# TLog_TopBat.net
KiCad netlist of a schematic drawn in EAGLE
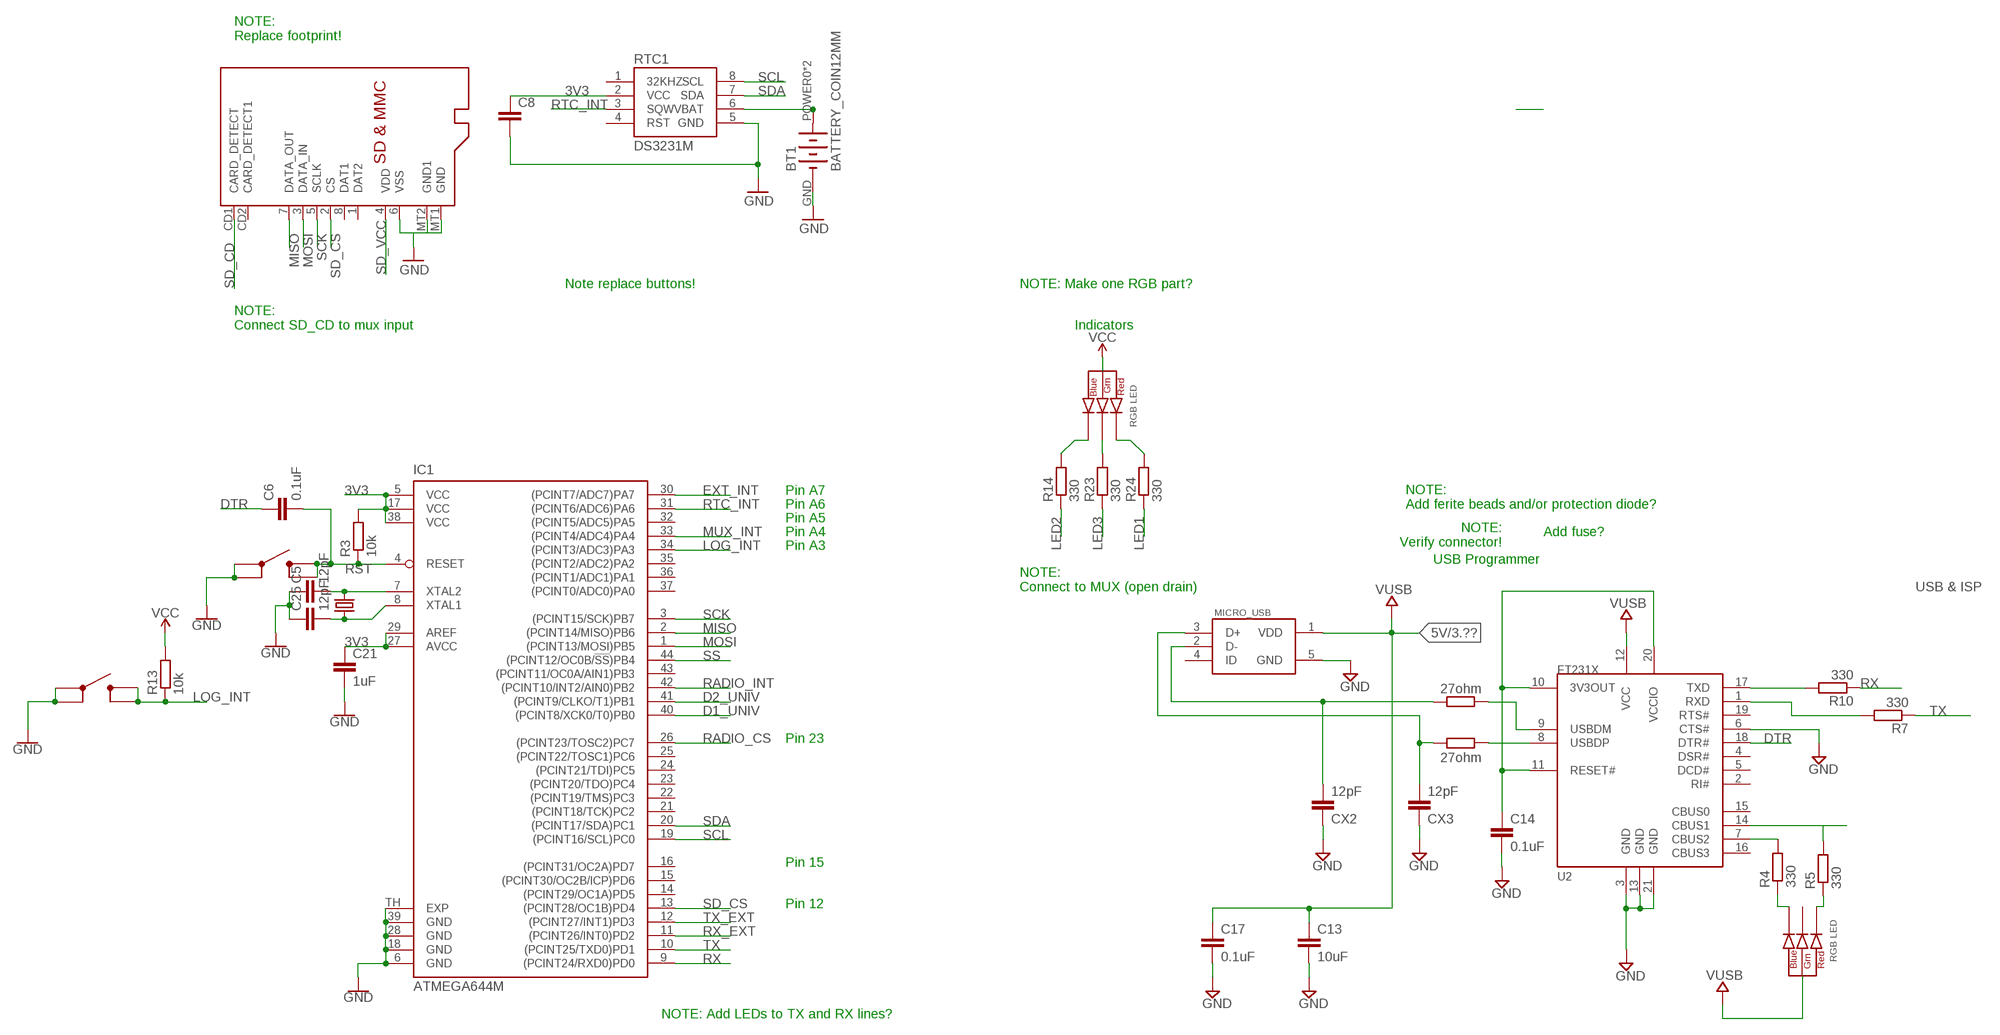
[diagram p0: schematic, sheet 1]
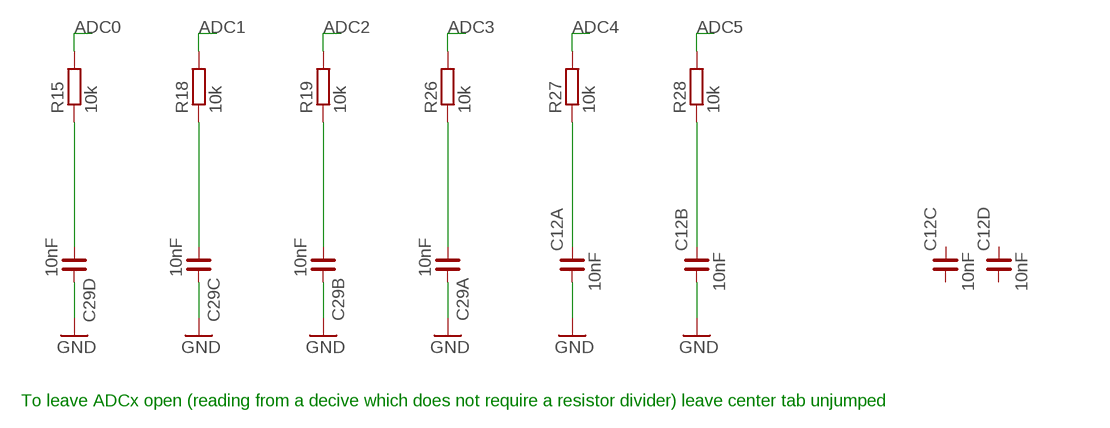
[diagram p1: schematic, sheet 2]
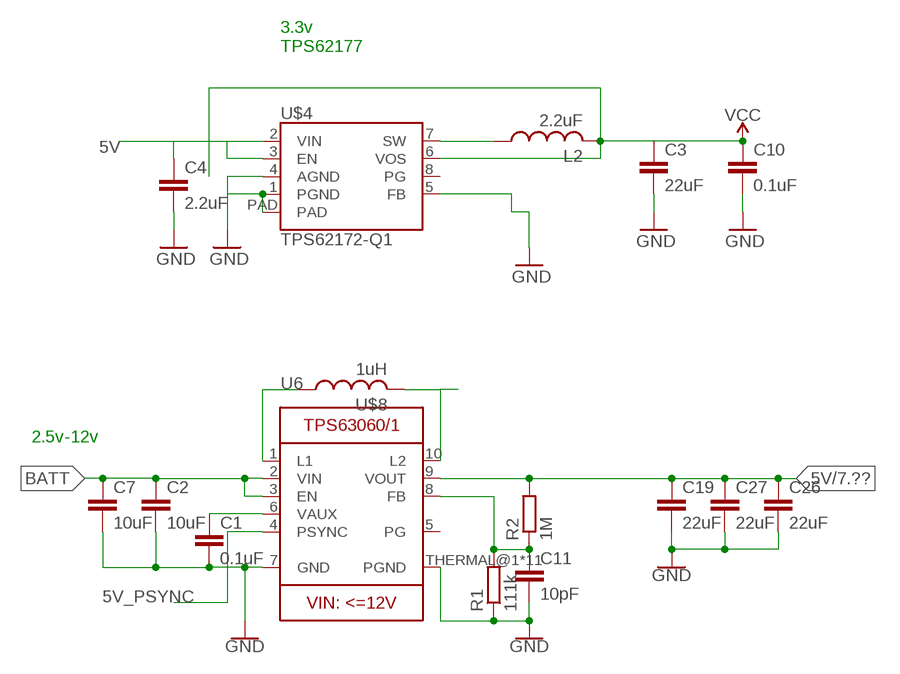
[diagram p2: schematic, sheet 3]
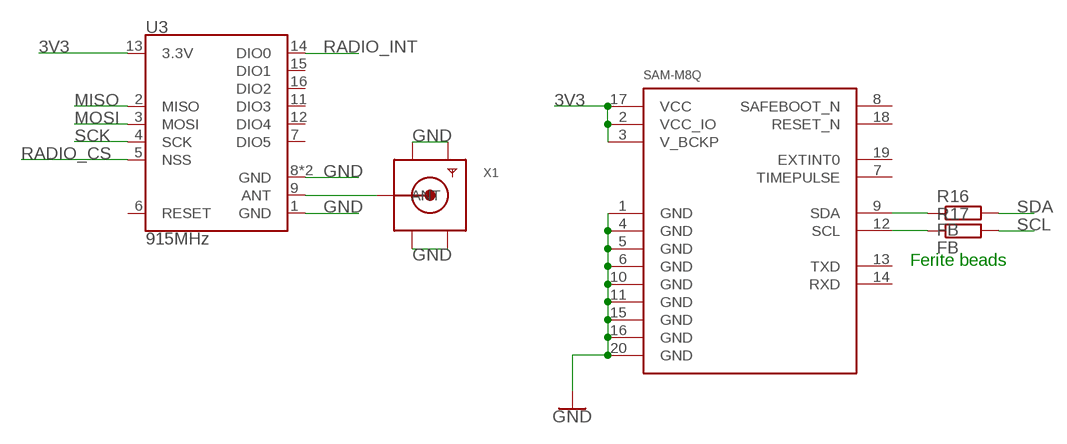
[diagram p3: schematic, sheet 4]
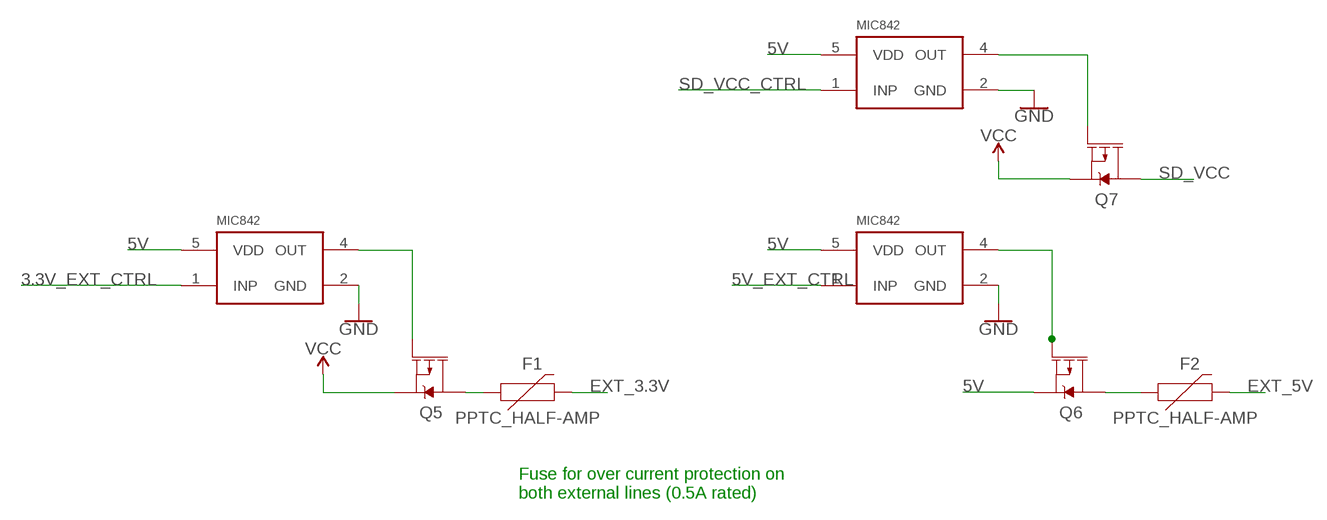
[diagram p4: schematic, sheet 5]
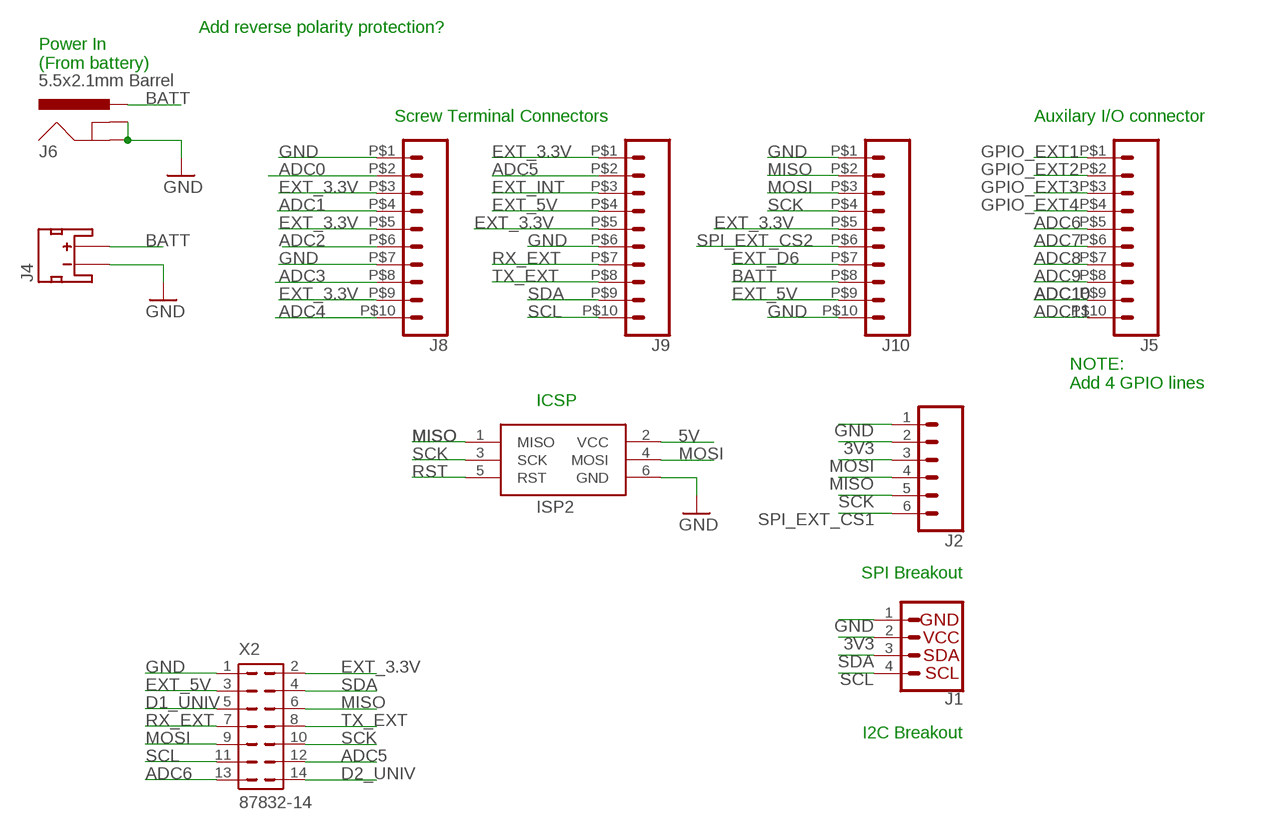
[diagram p5: schematic, sheet 6]
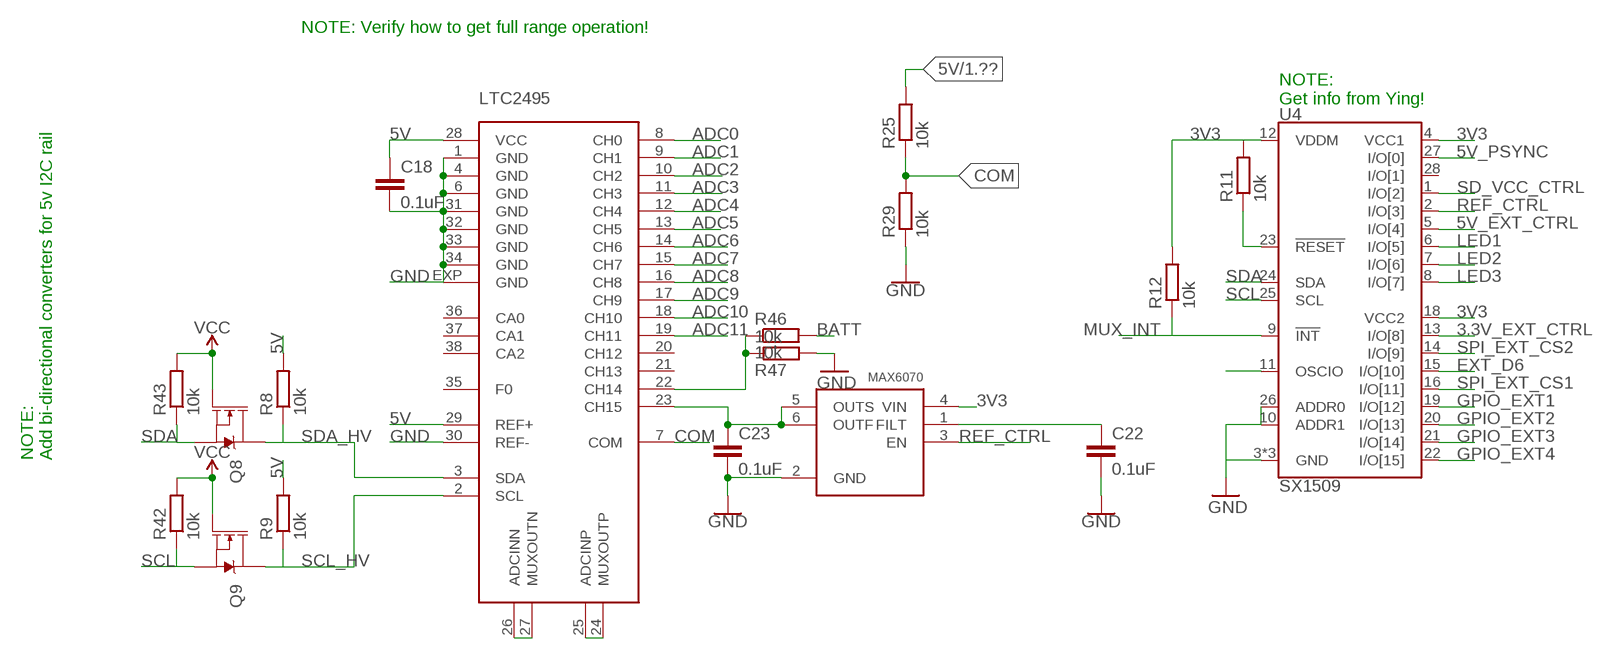
[diagram p6: schematic, sheet 7]

(export (version "E")
  (design (tool "Eeschema 10.0.6"))
  (components
    (comp (ref "C18")
      (value "0.1uF")
      (footprint "eagle-import:C0603")
      (fields (field (name "MF") "Samsung") (field (name "MPN") "CL10B104KO8NNNC"))
      (libsource (lib "eagle-import") (part "C-EUC06030.1UF"))
    )
    (comp (ref "C22")
      (value "0.1uF")
      (footprint "eagle-import:C0603")
      (fields (field (name "MF") "Samsung") (field (name "MPN") "CL10B104KO8NNNC"))
      (libsource (lib "eagle-import") (part "C-EUC06030.1UF"))
    )
    (comp (ref "C23")
      (value "0.1uF")
      (footprint "eagle-import:C0603")
      (fields (field (name "MF") "Samsung") (field (name "MPN") "CL10B104KO8NNNC"))
      (libsource (lib "eagle-import") (part "C-EUC06030.1UF"))
    )
    (comp (ref "Q8")
      (value "MOSFET-NCH-BSS138")
      (footprint "eagle-import:SOT23-3")
      (fields (field (name "MF") "ON Semiconductor") (field (name "MPN") "BSS138LT3G"))
      (libsource (lib "eagle-import") (part "MOSFET-NCH-BSS138"))
    )
    (comp (ref "Q9")
      (value "MOSFET-NCH-BSS138")
      (footprint "eagle-import:SOT23-3")
      (fields (field (name "MF") "ON Semiconductor") (field (name "MPN") "BSS138LT3G"))
      (libsource (lib "eagle-import") (part "MOSFET-NCH-BSS138"))
    )
    (comp (ref "R8")
      (value "10k")
      (footprint "eagle-import:R0603")
      (fields (field (name "MF") "Yageo") (field (name "MPN") "RC0603FR-0710KL"))
      (libsource (lib "eagle-import") (part "R-EU_R060310K"))
    )
    (comp (ref "R9")
      (value "10k")
      (footprint "eagle-import:R0603")
      (fields (field (name "MF") "Yageo") (field (name "MPN") "RC0603FR-0710KL"))
      (libsource (lib "eagle-import") (part "R-EU_R060310K"))
    )
    (comp (ref "R11")
      (value "10k")
      (footprint "eagle-import:R0603")
      (fields (field (name "MF") "Yageo") (field (name "MPN") "RC0603FR-0710KL"))
      (libsource (lib "eagle-import") (part "R-EU_R060310K"))
    )
    (comp (ref "R12")
      (value "10k")
      (footprint "eagle-import:R0603")
      (fields (field (name "MF") "Yageo") (field (name "MPN") "RC0603FR-0710KL"))
      (libsource (lib "eagle-import") (part "R-EU_R060310K"))
    )
    (comp (ref "R25")
      (value "10k")
      (footprint "eagle-import:R0603")
      (fields (field (name "MF") "Yageo") (field (name "MPN") "RC0603FR-0710KL"))
      (libsource (lib "eagle-import") (part "R-EU_R060310K"))
    )
    (comp (ref "R29")
      (value "10k")
      (footprint "eagle-import:R0603")
      (fields (field (name "MF") "Yageo") (field (name "MPN") "RC0603FR-0710KL"))
      (libsource (lib "eagle-import") (part "R-EU_R060310K"))
    )
    (comp (ref "R42")
      (value "10k")
      (footprint "eagle-import:R0603")
      (fields (field (name "MF") "Yageo") (field (name "MPN") "RC0603FR-0710KL"))
      (libsource (lib "eagle-import") (part "R-EU_R060310K"))
    )
    (comp (ref "R43")
      (value "10k")
      (footprint "eagle-import:R0603")
      (fields (field (name "MF") "Yageo") (field (name "MPN") "RC0603FR-0710KL"))
      (libsource (lib "eagle-import") (part "R-EU_R060310K"))
    )
    (comp (ref "R46")
      (value "10k")
      (footprint "eagle-import:R0603")
      (fields (field (name "MF") "Yageo") (field (name "MPN") "RC0603FR-0710KL"))
      (libsource (lib "eagle-import") (part "R-EU_R060310K"))
    )
    (comp (ref "R47")
      (value "10k")
      (footprint "eagle-import:R0603")
      (fields (field (name "MF") "Yageo") (field (name "MPN") "RC0603FR-0710KL"))
      (libsource (lib "eagle-import") (part "R-EU_R060310K"))
    )
    (comp (ref "U$7")
      (value "LTC2495")
      (footprint "eagle-import:QFN38-5X7")
      (fields (field (name "MF") "LT") (field (name "MPN") "LTC2495IUHF#PBF"))
      (libsource (lib "eagle-import") (part "LTC2495"))
    )
    (comp (ref "U$10")
      (value "MAX6070AAUT18")
      (footprint "eagle-import:SOT23-6L")
      (fields (field (name "MF") "Maxim") (field (name "MPN") "MAX6070BAUT18+T"))
      (libsource (lib "eagle-import") (part "MAX6070AAUT18"))
    )
    (comp (ref "U4")
      (value "SX1509")
      (footprint "eagle-import:QFN-28")
      (fields (field (name "MF") "Semtech") (field (name "MPN") "SX1509BIULTRT"))
      (libsource (lib "eagle-import") (part "SX1509"))
    )
    (comp (ref "ISP2")
      (value "AVRISP-6")
      (footprint "eagle-import:AVRISP")
      (fields (field (name "MF") "Amphenol") (field (name "MPN") "67997-206HLF"))
      (libsource (lib "eagle-import") (part "AVRISP-6"))
    )
    (comp (ref "J1")
      (value "I2C_STANDARD")
      (footprint "eagle-import:1X04")
      (libsource (lib "eagle-import") (part "I2C_STANDARD"))
    )
    (comp (ref "J2")
      (value "CONN_06SILK_FEMALE_PTH")
      (footprint "eagle-import:1X06")
      (libsource (lib "eagle-import") (part "CONN_06SILK_FEMALE_PTH"))
    )
    (comp (ref "J4")
      (value "JST_2MM_MALE")
      (footprint "eagle-import:JST-2-SMD")
      (fields (field (name "MF") "JST") (field (name "MPN") "S2B-PH-SM4-TB(LF)(SN)"))
      (libsource (lib "eagle-import") (part "JST_2MM_MALE"))
    )
    (comp (ref "J5")
      (value "CONN_103.5MM")
      (footprint "eagle-import:1X10_3.5MM_SCREW")
      (fields (field (name "MF") "On Shore Technology") (field (name "MPN") "OSTTE100104"))
      (libsource (lib "eagle-import") (part "CONN_103.5MM"))
    )
    (comp (ref "J6")
      (value "5.5x2.1mm Barrel")
      (footprint "eagle-import:POWER_JACK_SMD")
      (fields (field (name "MF") "Wurth") (field (name "MPN") "694106106102"))
      (libsource (lib "eagle-import") (part "POWER_JACKSMD"))
    )
    (comp (ref "J8")
      (value "CONN_103.5MM")
      (footprint "eagle-import:1X10_3.5MM_SCREW")
      (fields (field (name "MF") "On Shore Technology") (field (name "MPN") "OSTTE100104"))
      (libsource (lib "eagle-import") (part "CONN_103.5MM"))
    )
    (comp (ref "J9")
      (value "CONN_103.5MM")
      (footprint "eagle-import:1X10_3.5MM_SCREW")
      (fields (field (name "MF") "On Shore Technology") (field (name "MPN") "OSTTE100104"))
      (libsource (lib "eagle-import") (part "CONN_103.5MM"))
    )
    (comp (ref "J10")
      (value "CONN_103.5MM")
      (footprint "eagle-import:1X10_3.5MM_SCREW")
      (fields (field (name "MF") "On Shore Technology") (field (name "MPN") "OSTTE100104"))
      (libsource (lib "eagle-import") (part "CONN_103.5MM"))
    )
    (comp (ref "X2")
      (value "87832-14")
      (footprint "eagle-import:87832-14")
      (fields (field (name "MF") "Molex") (field (name "MPN") "0791091006"))
      (libsource (lib "eagle-import") (part "87832-14"))
    )
    (comp (ref "C12")
      (value "10nF")
      (footprint "eagle-import:CECJ-1206")
      (fields
        (field (name "DIGIKEY") "445-1854-1-ND")
        (field (name "MF") "TDK")
        (field (name "MPN") "CKCA43X7R1H103M100AA")
      )
      (libsource (lib "eagle-import") (part "CCA_ECJ-1206"))
    )
    (comp (ref "C29")
      (value "10nF")
      (footprint "eagle-import:CECJ-1206")
      (fields
        (field (name "DIGIKEY") "445-1854-1-ND")
        (field (name "MF") "TDK")
        (field (name "MPN") "CKCA43X7R1H103M100AA")
      )
      (libsource (lib "eagle-import") (part "CCA_ECJ-1206"))
    )
    (comp (ref "R15")
      (value "10k")
      (footprint "eagle-import:R0603")
      (fields (field (name "MF") "Yageo") (field (name "MPN") "RC0603FR-0710KL"))
      (libsource (lib "eagle-import") (part "R-EU_R060310K"))
    )
    (comp (ref "R18")
      (value "10k")
      (footprint "eagle-import:R0603")
      (fields (field (name "MF") "Yageo") (field (name "MPN") "RC0603FR-0710KL"))
      (libsource (lib "eagle-import") (part "R-EU_R060310K"))
    )
    (comp (ref "R19")
      (value "10k")
      (footprint "eagle-import:R0603")
      (fields (field (name "MF") "Yageo") (field (name "MPN") "RC0603FR-0710KL"))
      (libsource (lib "eagle-import") (part "R-EU_R060310K"))
    )
    (comp (ref "R26")
      (value "10k")
      (footprint "eagle-import:R0603")
      (fields (field (name "MF") "Yageo") (field (name "MPN") "RC0603FR-0710KL"))
      (libsource (lib "eagle-import") (part "R-EU_R060310K"))
    )
    (comp (ref "R27")
      (value "10k")
      (footprint "eagle-import:R0603")
      (fields (field (name "MF") "Yageo") (field (name "MPN") "RC0603FR-0710KL"))
      (libsource (lib "eagle-import") (part "R-EU_R060310K"))
    )
    (comp (ref "R28")
      (value "10k")
      (footprint "eagle-import:R0603")
      (fields (field (name "MF") "Yageo") (field (name "MPN") "RC0603FR-0710KL"))
      (libsource (lib "eagle-import") (part "R-EU_R060310K"))
    )
    (comp (ref "F1")
      (value "PPTC_HALF-AMP")
      (footprint "eagle-import:1206")
      (fields (field (name "MF") "Bourns") (field (name "MPN") "MF-NSMF020-2"))
      (libsource (lib "eagle-import") (part "PPTC_HALF-AMP"))
    )
    (comp (ref "F2")
      (value "PPTC_HALF-AMP")
      (footprint "eagle-import:1206")
      (fields (field (name "MF") "Bourns") (field (name "MPN") "MF-NSMF020-2"))
      (libsource (lib "eagle-import") (part "PPTC_HALF-AMP"))
    )
    (comp (ref "Q5")
      (value "MOSFET_PCH-IRLML2244")
      (footprint "eagle-import:SOT23-3")
      (fields (field (name "MF") "Fairchild") (field (name "MPN") "FDN360P"))
      (libsource (lib "eagle-import") (part "MOSFET_PCH-IRLML2244"))
    )
    (comp (ref "Q6")
      (value "MOSFET_PCH-IRLML2244")
      (footprint "eagle-import:SOT23-3")
      (fields (field (name "MF") "Fairchild") (field (name "MPN") "FDN360P"))
      (libsource (lib "eagle-import") (part "MOSFET_PCH-IRLML2244"))
    )
    (comp (ref "Q7")
      (value "MOSFET_PCH-IRLML2244")
      (footprint "eagle-import:SOT23-3")
      (fields (field (name "MF") "Fairchild") (field (name "MPN") "FDN360P"))
      (libsource (lib "eagle-import") (part "MOSFET_PCH-IRLML2244"))
    )
    (comp (ref "U$17")
      (value "MIC842")
      (footprint "eagle-import:DCK_R-PDSO-G5")
      (libsource (lib "eagle-import") (part "MIC842"))
    )
    (comp (ref "U$18")
      (value "MIC842")
      (footprint "eagle-import:DCK_R-PDSO-G5")
      (libsource (lib "eagle-import") (part "MIC842"))
    )
    (comp (ref "U$19")
      (value "MIC842")
      (footprint "eagle-import:DCK_R-PDSO-G5")
      (libsource (lib "eagle-import") (part "MIC842"))
    )
    (comp (ref "R16")
      (value "FB")
      (footprint "eagle-import:R0603")
      (fields (field (name "MF") "Samsung") (field (name "MPN") "CIC10P471NC"))
      (libsource (lib "eagle-import") (part "rcl_R-EU_R0603"))
    )
    (comp (ref "R17")
      (value "FB")
      (footprint "eagle-import:R0603")
      (fields (field (name "MF") "Samsung") (field (name "MPN") "CIC10P471NC"))
      (libsource (lib "eagle-import") (part "rcl_R-EU_R0603"))
    )
    (comp (ref "U$6")
      (value "SAM-M8Q")
      (footprint "eagle-import:SAM-M8Q")
      (fields (field (name "MPN") "SAM-M8Q-0") (field (name "MF") "UBlox"))
      (libsource (lib "eagle-import") (part "SAM-M8Q"))
    )
    (comp (ref "U3")
      (value "915MHz")
      (footprint "eagle-import:RFM69HCW-XXXS2")
      (libsource (lib "eagle-import") (part "RFM69HCW-915"))
    )
    (comp (ref "X1")
      (value "SMA_EDGE")
      (footprint "eagle-import:ADAFRUIT_SMA_EDGELAUNCH")
      (fields (field (name "MF") "RF Solutions") (field (name "MPN") "CON-SMA-EDGE-S"))
      (libsource (lib "eagle-import") (part "SMA_EDGE"))
    )
    (comp (ref "BT1")
      (value "BATTERY_COIN12MM")
      (footprint "eagle-import:AWICKERT_LINX_BAT-HLD-012-SMT")
      (fields (field (name "MF") "Linx") (field (name "MPN") "BAT-HLD-012-SMT"))
      (libsource (lib "eagle-import") (part "BATTERY_COIN12MM"))
    )
    (comp (ref "C5")
      (value "12pF")
      (footprint "eagle-import:C0603")
      (fields
        (field (name "MF") "Samsung")
        (field (name "MPN") "CL10C120JB8NNNC")
        (field (name "DIGIKEY") "1276-1254-1-ND")
        (field (name "MF_1") "Samsung")
        (field (name "MPN_1") "CL10C120JB8NNNC")
      )
      (libsource (lib "eagle-import") (part "C-EUC060312PF"))
    )
    (comp (ref "C6")
      (value "0.1uF")
      (footprint "eagle-import:C0603")
      (fields (field (name "MF") "Samsung") (field (name "MPN") "CL10B104KO8NNNC"))
      (libsource (lib "eagle-import") (part "C-EUC06030.1UF"))
    )
    (comp (ref "C8")
      (value "C-EUC0603")
      (footprint "eagle-import:C0603")
      (libsource (lib "eagle-import") (part "C-EUC0603"))
    )
    (comp (ref "C13")
      (value "10uF")
      (footprint "eagle-import:C0805")
      (fields (field (name "MF") "Samsung") (field (name "MPN") "CL21A106KQCLRNC"))
      (libsource (lib "eagle-import") (part "C-EUC080510UF"))
    )
    (comp (ref "C14")
      (value "0.1uF")
      (footprint "eagle-import:C0603")
      (fields (field (name "MF") "Samsung") (field (name "MPN") "CL10B104KO8NNNC"))
      (libsource (lib "eagle-import") (part "C-EUC06030.1UF"))
    )
    (comp (ref "C17")
      (value "0.1uF")
      (footprint "eagle-import:C0603")
      (fields (field (name "MF") "Samsung") (field (name "MPN") "CL10B104KO8NNNC"))
      (libsource (lib "eagle-import") (part "C-EUC06030.1UF"))
    )
    (comp (ref "C21")
      (value "1uF")
      (footprint "eagle-import:C0603")
      (fields
        (field (name "MF") "Samsung")
        (field (name "MPN") "1276-6524-1-ND")
        (field (name "DIGIKEY") "1276-6524-1-ND")
        (field (name "MF_1") "Samsung")
        (field (name "MPN_1") "CL10B105MO8NNWC")
      )
      (libsource (lib "eagle-import") (part "C-EUC06031UF"))
    )
    (comp (ref "C25")
      (value "12pF")
      (footprint "eagle-import:C0603")
      (fields
        (field (name "MF") "Samsung")
        (field (name "MPN") "CL10C120JB8NNNC")
        (field (name "DIGIKEY") "1276-1254-1-ND")
        (field (name "MF_1") "Samsung")
        (field (name "MPN_1") "CL10C120JB8NNNC")
      )
      (libsource (lib "eagle-import") (part "C-EUC060312PF"))
    )
    (comp (ref "CX2")
      (value "12pF")
      (footprint "eagle-import:C0603")
      (fields (field (name "MF") "Samsung") (field (name "MPN") "CL10C120JB8NNNC"))
      (libsource (lib "eagle-import") (part "C-EUC060312PF"))
    )
    (comp (ref "CX3")
      (value "12pF")
      (footprint "eagle-import:C0603")
      (fields (field (name "MF") "Samsung") (field (name "MPN") "CL10C120JB8NNNC"))
      (libsource (lib "eagle-import") (part "C-EUC060312PF"))
    )
    (comp (ref "D+")
      (value "27ohm")
      (footprint "eagle-import:R0603")
      (fields
        (field (name "MF") "Yageo")
        (field (name "MPN") "RC0603FR-0727RL")
        (field (name "VALUE_PART") "27")
      )
      (libsource (lib "eagle-import") (part "R-EU_R060327"))
    )
    (comp (ref "D-")
      (value "27ohm")
      (footprint "eagle-import:R0603")
      (fields
        (field (name "MF") "Yageo")
        (field (name "MPN") "RC0603FR-0727RL")
        (field (name "VALUE_PART") "27")
      )
      (libsource (lib "eagle-import") (part "R-EU_R060327"))
    )
    (comp (ref "IC1")
      (value "ATMEGA644M")
      (footprint "eagle-import:MLF44-TH")
      (fields (field (name "MF") "Atmel") (field (name "MPN") "ATMEGA644PA-MUR"))
      (libsource (lib "eagle-import") (part "ATMEGA644M"))
    )
    (comp (ref "MICRO_USB")
      (value "MICRO_USB_LONGPADS")
      (footprint "eagle-import:10118194-0001LF_10118194-0001LF_LONGER_PADS")
      (libsource (lib "eagle-import") (part "MICRO_USB_LONGPADS"))
    )
    (comp (ref "R3")
      (value "10k")
      (footprint "eagle-import:R0603")
      (fields
        (field (name "MF") "Yageo")
        (field (name "MPN") "RC0603FR-0710KL")
        (field (name "DIGIKEY") "311-10.0KHRCT-ND")
      )
      (libsource (lib "eagle-import") (part "R-EU_R060310K"))
    )
    (comp (ref "R4")
      (value "330")
      (footprint "eagle-import:R0603")
      (fields
        (field (name "MF") "Yageo")
        (field (name "MPN") "RC0603FR-07330RL")
        (field (name "MPN_1") "RC0603FR-07330RL")
      )
      (libsource (lib "eagle-import") (part "R-EU_R0603330"))
    )
    (comp (ref "R5")
      (value "330")
      (footprint "eagle-import:R0603")
      (fields
        (field (name "MF") "Yageo")
        (field (name "MPN") "RC0603FR-07330RL")
        (field (name "DIGIKEY") "311-330HRCT-ND")
        (field (name "MF_1") "Yageo")
        (field (name "MPN_1") "RC0603FR-07330RL")
      )
      (libsource (lib "eagle-import") (part "R-EU_R0603330"))
    )
    (comp (ref "R7")
      (value "330")
      (footprint "eagle-import:R0603")
      (fields
        (field (name "MF") "Yageo")
        (field (name "MPN") "RC0603FR-07330RL")
        (field (name "MPN_1") "RC0603FR-07330RL")
      )
      (libsource (lib "eagle-import") (part "R-EU_R0603330"))
    )
    (comp (ref "R10")
      (value "330")
      (footprint "eagle-import:R0603")
      (fields
        (field (name "MF") "Yageo")
        (field (name "MPN") "RC0603FR-07330RL")
        (field (name "MPN_1") "RC0603FR-07330RL")
      )
      (libsource (lib "eagle-import") (part "R-EU_R0603330"))
    )
    (comp (ref "R13")
      (value "10k")
      (footprint "eagle-import:R0603")
      (fields
        (field (name "MF") "Yageo")
        (field (name "MPN") "RC0603FR-0710KL")
        (field (name "DIGIKEY") "311-10.0KHRCT-ND")
      )
      (libsource (lib "eagle-import") (part "R-EU_R060310K"))
    )
    (comp (ref "R14")
      (value "330")
      (footprint "eagle-import:R0603")
      (fields
        (field (name "MF") "Yageo")
        (field (name "MPN") "RC0603FR-07330RL")
        (field (name "MPN_1") "RC0603FR-07330RL")
      )
      (libsource (lib "eagle-import") (part "R-EU_R0603330"))
    )
    (comp (ref "R23")
      (value "330")
      (footprint "eagle-import:R0603")
      (fields
        (field (name "MF") "Yageo")
        (field (name "MPN") "RC0603FR-07330RL")
        (field (name "MPN_1") "RC0603FR-07330RL")
      )
      (libsource (lib "eagle-import") (part "R-EU_R0603330"))
    )
    (comp (ref "R24")
      (value "330")
      (footprint "eagle-import:R0603")
      (fields
        (field (name "MF") "Yageo")
        (field (name "MPN") "RC0603FR-07330RL")
        (field (name "MPN_1") "RC0603FR-07330RL")
      )
      (libsource (lib "eagle-import") (part "R-EU_R0603330"))
    )
    (comp (ref "RTC1")
      (value "DS3231M")
      (footprint "eagle-import:SO08")
      (fields (field (name "MF") "Maxim") (field (name "MPN") "DS3231MZ+"))
      (libsource (lib "eagle-import") (part "DS3231M"))
    )
    (comp (ref "U$1")
      (value "CRYSTALTXC_8MHZ")
      (footprint "eagle-import:CRYSTAL_5X3.2_2-SMD")
      (fields (field (name "MF") "TXC") (field (name "MPN") "7A-8.000MAAE-T"))
      (libsource (lib "eagle-import") (part "CRYSTALTXC_8MHZ"))
    )
    (comp (ref "U$2")
      (value "MICROSD")
      (footprint "eagle-import:MICROSD")
      (fields (field (name "MF") "3M") (field (name "MPN") "2908-05WB-MG"))
      (libsource (lib "eagle-import") (part "MICROSD"))
    )
    (comp (ref "U$5")
      (value "BUTTON4.2X3.2")
      (footprint "eagle-import:SWITCH_4.2X3.2")
      (libsource (lib "eagle-import") (part "BUTTON4.2X3.2"))
    )
    (comp (ref "U$9")
      (value "BUTTON4.2X3.2")
      (footprint "eagle-import:SWITCH_4.2X3.2")
      (libsource (lib "eagle-import") (part "BUTTON4.2X3.2"))
    )
    (comp (ref "U$15")
      (value "CLVBA-FKA")
      (footprint "eagle-import:CLVBA-FKA")
      (fields (field (name "MF") "Cree") (field (name "MPN") "CLVBA-FKA-CAEDH8BBB7A363"))
      (libsource (lib "eagle-import") (part "CLVBA-FKA"))
    )
    (comp (ref "U$16")
      (value "CLVBA-FKA")
      (footprint "eagle-import:CLVBA-FKA")
      (fields (field (name "MF") "Cree") (field (name "MPN") "CLVBA-FKA-CAEDH8BBB7A363"))
      (libsource (lib "eagle-import") (part "CLVBA-FKA"))
    )
    (comp (ref "U2")
      (value "FT231X-Q")
      (footprint "eagle-import:QFN20")
      (fields (field (name "MF") "FTDI") (field (name "MPN") "FT231XQ-R"))
      (libsource (lib "eagle-import") (part "FT231X-Q"))
    )
    (comp (ref "C1")
      (value "0.1uF")
      (footprint "eagle-import:C0603")
      (fields (field (name "MF") "Samsung") (field (name "MPN") "CL10B104KO8NNNC"))
      (libsource (lib "eagle-import") (part "C-EUC06030.1UF"))
    )
    (comp (ref "C2")
      (value "10uF")
      (footprint "eagle-import:C0805")
      (fields (field (name "MF") "Samsung") (field (name "MPN") "CL21A106KQCLRNC"))
      (libsource (lib "eagle-import") (part "C-EUC080510UF"))
    )
    (comp (ref "C3")
      (value "22uF")
      (footprint "eagle-import:C0805")
      (fields (field (name "MF") "Samsung") (field (name "MPN") "CL21A226KQCLRNC"))
      (libsource (lib "eagle-import") (part "C-EUC080522UF"))
    )
    (comp (ref "C4")
      (value "2.2uF")
      (footprint "eagle-import:C0805")
      (fields (field (name "MF") "Samsung") (field (name "MPN") "CL21A106KQCLRNC"))
      (libsource (lib "eagle-import") (part "C-EUC080510UF"))
    )
    (comp (ref "C7")
      (value "10uF")
      (footprint "eagle-import:C0805")
      (fields (field (name "MF") "Samsung") (field (name "MPN") "CL21A106KQCLRNC"))
      (libsource (lib "eagle-import") (part "C-EUC080510UF"))
    )
    (comp (ref "C10")
      (value "0.1uF")
      (footprint "eagle-import:C0603")
      (fields (field (name "MF") "Samsung") (field (name "MPN") "CL10B104KO8NNNC"))
      (libsource (lib "eagle-import") (part "C-EUC06030.1UF"))
    )
    (comp (ref "C11")
      (value "10pF")
      (footprint "eagle-import:C0603")
      (fields (field (name "MF") "Samsung") (field (name "MPN") "CL10C120JB8NNNC"))
      (libsource (lib "eagle-import") (part "C-EUC060312PF"))
    )
    (comp (ref "C19")
      (value "22uF")
      (footprint "eagle-import:C0805")
      (fields (field (name "MF") "Samsung") (field (name "MPN") "CL21A226KQCLRNC"))
      (libsource (lib "eagle-import") (part "C-EUC080522UF"))
    )
    (comp (ref "C26")
      (value "22uF")
      (footprint "eagle-import:C0805")
      (fields (field (name "MF") "Samsung") (field (name "MPN") "CL21A226KQCLRNC"))
      (libsource (lib "eagle-import") (part "C-EUC080522UF"))
    )
    (comp (ref "C27")
      (value "22uF")
      (footprint "eagle-import:C0805")
      (fields (field (name "MF") "Samsung") (field (name "MPN") "CL21A226KQCLRNC"))
      (libsource (lib "eagle-import") (part "C-EUC080522UF"))
    )
    (comp (ref "L2")
      (value "2.2uF")
      (footprint "eagle-import:0806")
      (fields (field (name "MF") "Wurth") (field (name "MPN") "74438343022"))
      (libsource (lib "eagle-import") (part "INDUCTOR0806"))
    )
    (comp (ref "R1")
      (value "111k")
      (footprint "eagle-import:R0603")
      (fields
        (field (name "DIGIKEY") "311-143KHRCT-ND")
        (field (name "MF") "Yageo")
        (field (name "MPN") "RC0603FR-07143KL")
      )
      (libsource (lib "eagle-import") (part "R-EU_R0603"))
    )
    (comp (ref "R2")
      (value "1M")
      (footprint "eagle-import:R0603")
      (fields
        (field (name "DIGIKEY") "311-953KHRCT-ND")
        (field (name "MF") "Yageo")
        (field (name "MPN") "RC0603FR-07953KL")
      )
      (libsource (lib "eagle-import") (part "R-EU_R0603"))
    )
    (comp (ref "U$4")
      (value "TPS62172-Q1")
      (footprint "eagle-import:WSON-8-PAD")
      (fields (field (name "MF") "TI") (field (name "MPN") "TPS62172QDSGRQ1"))
      (libsource (lib "eagle-import") (part "TPS6217-Q12"))
    )
    (comp (ref "U$8")
      (value "1uH")
      (footprint "eagle-import:WE-MAIA(4.1X4.1)")
      (fields (field (name "MF") "Wurth") (field (name "MPN") "78438356010"))
      (libsource (lib "eagle-import") (part "INDUCTORMAIA_4.1X4.1"))
    )
    (comp (ref "U6")
      (value "TPS63060")
      (footprint "eagle-import:PWSON-N10")
      (fields (field (name "MF") "TI") (field (name "MPN") "TPS63060DSCR"))
      (libsource (lib "eagle-import") (part "TPS63060"))
    )
  )
  (nets
    (net (code "1") (name "3.3V_EXT_CTRL") (class "Default")
      (node (ref "U$18") (pin "1") (pinfunction "INP_1") (pintype "input"))
      (node (ref "U4") (pin "13") (pinfunction "I/O[8]_13") (pintype "bidirectional"))
    )
    (net (code "2") (name "3V3") (class "Default")
      (node (ref "C10") (pin "1") (pinfunction "1_1") (pintype "passive"))
      (node (ref "C21") (pin "1") (pinfunction "1_1") (pintype "passive"))
      (node (ref "C3") (pin "1") (pinfunction "1_1") (pintype "passive"))
      (node (ref "C8") (pin "1") (pinfunction "1_1") (pintype "passive"))
      (node (ref "IC1") (pin "17") (pinfunction "VCC_17") (pintype "power_in"))
      (node (ref "IC1") (pin "27") (pinfunction "AVCC_27") (pintype "power_in"))
      (node (ref "IC1") (pin "29") (pinfunction "AREF_29") (pintype "passive"))
      (node (ref "IC1") (pin "38") (pinfunction "VCC_38") (pintype "power_in"))
      (node (ref "IC1") (pin "5") (pinfunction "VCC_5") (pintype "power_in"))
      (node (ref "J1") (pin "2") (pinfunction "2_2") (pintype "power_in"))
      (node (ref "J2") (pin "2") (pinfunction "2_2") (pintype "passive"))
      (node (ref "L2") (pin "P$2") (pinfunction "2_P$2") (pintype "passive"))
      (node (ref "Q5") (pin "2") (pinfunction "S_2") (pintype "bidirectional"))
      (node (ref "Q7") (pin "2") (pinfunction "S_2") (pintype "bidirectional"))
      (node (ref "Q8") (pin "1") (pinfunction "G_1") (pintype "bidirectional"))
      (node (ref "Q9") (pin "1") (pinfunction "G_1") (pintype "bidirectional"))
      (node (ref "R11") (pin "2") (pinfunction "2_2") (pintype "passive"))
      (node (ref "R12") (pin "2") (pinfunction "2_2") (pintype "passive"))
      (node (ref "R13") (pin "2") (pinfunction "2_2") (pintype "passive"))
      (node (ref "R3") (pin "2") (pinfunction "2_2") (pintype "passive"))
      (node (ref "R42") (pin "2") (pinfunction "2_2") (pintype "passive"))
      (node (ref "R43") (pin "2") (pinfunction "2_2") (pintype "passive"))
      (node (ref "RTC1") (pin "2") (pinfunction "VCC_2") (pintype "power_in"))
      (node (ref "U$10") (pin "4") (pinfunction "VIN_4") (pintype "bidirectional"))
      (node (ref "U$15") (pin "2") (pinfunction "ANODE_2") (pintype "bidirectional"))
      (node (ref "U$4") (pin "6") (pinfunction "VOS_6") (pintype "bidirectional"))
      (node (ref "U$6") (pin "17") (pinfunction "VCC_17") (pintype "bidirectional"))
      (node (ref "U$6") (pin "2") (pinfunction "VCC_IO_2") (pintype "bidirectional"))
      (node (ref "U$6") (pin "3") (pinfunction "V_BCKP_3") (pintype "bidirectional"))
      (node (ref "U3") (pin "13") (pinfunction "3.3V_13") (pintype "power_in"))
      (node (ref "U4") (pin "12") (pinfunction "VDDM_12") (pintype "bidirectional"))
      (node (ref "U4") (pin "18") (pinfunction "VCC2_18") (pintype "bidirectional"))
      (node (ref "U4") (pin "4") (pinfunction "VCC1_4") (pintype "bidirectional"))
    )
    (net (code "3") (name "5V") (class "Default")
      (node (ref "C13") (pin "1") (pinfunction "1_1") (pintype "passive"))
      (node (ref "C17") (pin "1") (pinfunction "1_1") (pintype "passive"))
      (node (ref "C18") (pin "1") (pinfunction "1_1") (pintype "passive"))
      (node (ref "C19") (pin "1") (pinfunction "1_1") (pintype "passive"))
      (node (ref "C26") (pin "1") (pinfunction "1_1") (pintype "passive"))
      (node (ref "C27") (pin "1") (pinfunction "1_1") (pintype "passive"))
      (node (ref "C4") (pin "1") (pinfunction "1_1") (pintype "passive"))
      (node (ref "ISP2") (pin "2") (pinfunction "VCC_2") (pintype "power_in"))
      (node (ref "MICRO_USB") (pin "1") (pinfunction "VDD_1") (pintype "power_in"))
      (node (ref "Q6") (pin "2") (pinfunction "S_2") (pintype "bidirectional"))
      (node (ref "R2") (pin "2") (pinfunction "2_2") (pintype "passive"))
      (node (ref "R25") (pin "2") (pinfunction "2_2") (pintype "passive"))
      (node (ref "R8") (pin "2") (pinfunction "2_2") (pintype "passive"))
      (node (ref "R9") (pin "2") (pinfunction "2_2") (pintype "passive"))
      (node (ref "U$16") (pin "2") (pinfunction "ANODE_2") (pintype "bidirectional"))
      (node (ref "U$17") (pin "5") (pinfunction "VDD_5") (pintype "power_in"))
      (node (ref "U$18") (pin "5") (pinfunction "VDD_5") (pintype "power_in"))
      (node (ref "U$19") (pin "5") (pinfunction "VDD_5") (pintype "power_in"))
      (node (ref "U$4") (pin "2") (pinfunction "VIN_2") (pintype "bidirectional"))
      (node (ref "U$4") (pin "3") (pinfunction "EN_3") (pintype "bidirectional"))
      (node (ref "U$7") (pin "28") (pinfunction "VCC_28") (pintype "power_in"))
      (node (ref "U$7") (pin "29") (pinfunction "REF+_29") (pintype "input"))
      (node (ref "U2") (pin "12") (pinfunction "VCC_12") (pintype "bidirectional"))
      (node (ref "U6") (pin "9") (pinfunction "VOUT_9") (pintype "power_in"))
    )
    (net (code "4") (name "5V_EXT_CTRL") (class "Default")
      (node (ref "U$17") (pin "1") (pinfunction "INP_1") (pintype "input"))
      (node (ref "U4") (pin "5") (pinfunction "I/O[4]_5") (pintype "bidirectional"))
    )
    (net (code "5") (name "5V_PSYNC") (class "Default")
      (node (ref "U4") (pin "27") (pinfunction "I/O[0]_27") (pintype "bidirectional"))
      (node (ref "U6") (pin "4") (pinfunction "PSYNC_4") (pintype "input"))
    )
    (net (code "6") (name "ADC0") (class "Default")
      (node (ref "J8") (pin "P$2") (pinfunction "2_P$2") (pintype "passive"))
      (node (ref "R15") (pin "2") (pinfunction "2_2") (pintype "passive"))
      (node (ref "U$7") (pin "8") (pinfunction "CH0_8") (pintype "input"))
    )
    (net (code "7") (name "ADC1") (class "Default")
      (node (ref "J8") (pin "P$4") (pinfunction "4_P$4") (pintype "passive"))
      (node (ref "R18") (pin "2") (pinfunction "2_2") (pintype "passive"))
      (node (ref "U$7") (pin "9") (pinfunction "CH1_9") (pintype "input"))
    )
    (net (code "8") (name "ADC2") (class "Default")
      (node (ref "J8") (pin "P$6") (pinfunction "6_P$6") (pintype "passive"))
      (node (ref "R19") (pin "2") (pinfunction "2_2") (pintype "passive"))
      (node (ref "U$7") (pin "10") (pinfunction "CH2_10") (pintype "input"))
    )
    (net (code "9") (name "ADC3") (class "Default")
      (node (ref "J8") (pin "P$8") (pinfunction "8_P$8") (pintype "passive"))
      (node (ref "R26") (pin "2") (pinfunction "2_2") (pintype "passive"))
      (node (ref "U$7") (pin "11") (pinfunction "CH3_11") (pintype "input"))
    )
    (net (code "10") (name "ADC4") (class "Default")
      (node (ref "J8") (pin "P$10") (pinfunction "10_P$10") (pintype "passive"))
      (node (ref "R27") (pin "2") (pinfunction "2_2") (pintype "passive"))
      (node (ref "U$7") (pin "12") (pinfunction "CH4_12") (pintype "input"))
    )
    (net (code "11") (name "ADC5") (class "Default")
      (node (ref "J9") (pin "P$2") (pinfunction "2_P$2") (pintype "passive"))
      (node (ref "R28") (pin "2") (pinfunction "2_2") (pintype "passive"))
      (node (ref "U$7") (pin "13") (pinfunction "CH5_13") (pintype "input"))
      (node (ref "X2") (pin "12") (pinfunction "12_12") (pintype "passive"))
    )
    (net (code "12") (name "ADC6") (class "Default")
      (node (ref "J5") (pin "P$5") (pinfunction "5_P$5") (pintype "passive"))
      (node (ref "U$7") (pin "14") (pinfunction "CH6_14") (pintype "input"))
      (node (ref "X2") (pin "13") (pinfunction "13_13") (pintype "passive"))
    )
    (net (code "13") (name "ADC7") (class "Default")
      (node (ref "J5") (pin "P$6") (pinfunction "6_P$6") (pintype "passive"))
      (node (ref "U$7") (pin "15") (pinfunction "CH7_15") (pintype "input"))
    )
    (net (code "14") (name "ADC8") (class "Default")
      (node (ref "J5") (pin "P$7") (pinfunction "7_P$7") (pintype "passive"))
      (node (ref "U$7") (pin "16") (pinfunction "CH8_16") (pintype "input"))
    )
    (net (code "15") (name "ADC9") (class "Default")
      (node (ref "J5") (pin "P$8") (pinfunction "8_P$8") (pintype "passive"))
      (node (ref "U$7") (pin "17") (pinfunction "CH9_17") (pintype "input"))
    )
    (net (code "16") (name "ADC10") (class "Default")
      (node (ref "J5") (pin "P$9") (pinfunction "9_P$9") (pintype "passive"))
      (node (ref "U$7") (pin "18") (pinfunction "CH10_18") (pintype "input"))
    )
    (net (code "17") (name "ADC11") (class "Default")
      (node (ref "J5") (pin "P$10") (pinfunction "10_P$10") (pintype "passive"))
      (node (ref "U$7") (pin "19") (pinfunction "CH11_19") (pintype "input"))
    )
    (net (code "18") (name "BATT") (class "Default")
      (node (ref "C2") (pin "1") (pinfunction "1_1") (pintype "passive"))
      (node (ref "C7") (pin "1") (pinfunction "1_1") (pintype "passive"))
      (node (ref "J10") (pin "P$8") (pinfunction "8_P$8") (pintype "passive"))
      (node (ref "J4") (pin "2") (pinfunction "+_2") (pintype "bidirectional"))
      (node (ref "J6") (pin "VIN0") (pinfunction "PWR_VIN0") (pintype "bidirectional"))
      (node (ref "R46") (pin "2") (pinfunction "2_2") (pintype "passive"))
      (node (ref "U6") (pin "2") (pinfunction "VIN_2") (pintype "power_in"))
      (node (ref "U6") (pin "3") (pinfunction "EN_3") (pintype "input"))
    )
    (net (code "19") (name "COM") (class "Default")
      (node (ref "R25") (pin "1") (pinfunction "1_1") (pintype "passive"))
      (node (ref "R29") (pin "2") (pinfunction "2_2") (pintype "passive"))
      (node (ref "U$7") (pin "7") (pinfunction "COM_7") (pintype "input"))
    )
    (net (code "20") (name "D1_UNIV") (class "Default")
      (node (ref "IC1") (pin "40") (pinfunction "(PCINT8/XCK0/T0)PB0_40") (pintype "bidirectional"))
      (node (ref "X2") (pin "5") (pinfunction "5_5") (pintype "passive"))
    )
    (net (code "21") (name "D2_UNIV") (class "Default")
      (node (ref "IC1") (pin "41") (pinfunction "(PCINT9/CLKO/T1)PB1_41") (pintype "bidirectional"))
      (node (ref "X2") (pin "14") (pinfunction "14_14") (pintype "passive"))
    )
    (net (code "22") (name "DTR") (class "Default")
      (node (ref "C6") (pin "1") (pinfunction "1_1") (pintype "passive"))
      (node (ref "U2") (pin "18") (pinfunction "DTR#_18") (pintype "bidirectional"))
    )
    (net (code "23") (name "EXT_3.3V") (class "Default")
      (node (ref "F1") (pin "2") (pinfunction "2_2") (pintype "bidirectional"))
      (node (ref "J10") (pin "P$5") (pinfunction "5_P$5") (pintype "passive"))
      (node (ref "J8") (pin "P$3") (pinfunction "3_P$3") (pintype "passive"))
      (node (ref "J8") (pin "P$5") (pinfunction "5_P$5") (pintype "passive"))
      (node (ref "J8") (pin "P$9") (pinfunction "9_P$9") (pintype "passive"))
      (node (ref "J9") (pin "P$1") (pinfunction "1_P$1") (pintype "passive"))
      (node (ref "J9") (pin "P$5") (pinfunction "5_P$5") (pintype "passive"))
      (node (ref "X2") (pin "2") (pinfunction "2_2") (pintype "passive"))
    )
    (net (code "24") (name "EXT_5V") (class "Default")
      (node (ref "F2") (pin "2") (pinfunction "2_2") (pintype "bidirectional"))
      (node (ref "J10") (pin "P$9") (pinfunction "9_P$9") (pintype "passive"))
      (node (ref "J9") (pin "P$4") (pinfunction "4_P$4") (pintype "passive"))
      (node (ref "X2") (pin "3") (pinfunction "3_3") (pintype "passive"))
    )
    (net (code "25") (name "EXT_D6") (class "Default")
      (node (ref "J10") (pin "P$7") (pinfunction "7_P$7") (pintype "passive"))
      (node (ref "U4") (pin "15") (pinfunction "I/O[10]_15") (pintype "bidirectional"))
    )
    (net (code "26") (name "EXT_INT") (class "Default")
      (node (ref "IC1") (pin "30") (pinfunction "(PCINT7/ADC7)PA7_30") (pintype "bidirectional"))
      (node (ref "J9") (pin "P$3") (pinfunction "3_P$3") (pintype "passive"))
    )
    (net (code "27") (name "GND") (class "Default")
      (node (ref "BT1") (pin "GND") (pinfunction "-_GND") (pintype "passive"))
      (node (ref "C1") (pin "2") (pinfunction "2_2") (pintype "passive"))
      (node (ref "C10") (pin "2") (pinfunction "2_2") (pintype "passive"))
      (node (ref "C11") (pin "2") (pinfunction "2_2") (pintype "passive"))
      (node (ref "C12") (pin "A1") (pinfunction "1_A1") (pintype "passive"))
      (node (ref "C12") (pin "B1") (pinfunction "1_B1") (pintype "passive"))
      (node (ref "C13") (pin "2") (pinfunction "2_2") (pintype "passive"))
      (node (ref "C14") (pin "2") (pinfunction "2_2") (pintype "passive"))
      (node (ref "C17") (pin "2") (pinfunction "2_2") (pintype "passive"))
      (node (ref "C18") (pin "2") (pinfunction "2_2") (pintype "passive"))
      (node (ref "C19") (pin "2") (pinfunction "2_2") (pintype "passive"))
      (node (ref "C2") (pin "2") (pinfunction "2_2") (pintype "passive"))
      (node (ref "C21") (pin "2") (pinfunction "2_2") (pintype "passive"))
      (node (ref "C22") (pin "2") (pinfunction "2_2") (pintype "passive"))
      (node (ref "C23") (pin "2") (pinfunction "2_2") (pintype "passive"))
      (node (ref "C25") (pin "1") (pinfunction "1_1") (pintype "passive"))
      (node (ref "C26") (pin "2") (pinfunction "2_2") (pintype "passive"))
      (node (ref "C27") (pin "2") (pinfunction "2_2") (pintype "passive"))
      (node (ref "C29") (pin "A2") (pinfunction "2_A2") (pintype "passive"))
      (node (ref "C29") (pin "B2") (pinfunction "2_B2") (pintype "passive"))
      (node (ref "C29") (pin "C2") (pinfunction "2_C2") (pintype "passive"))
      (node (ref "C29") (pin "D2") (pinfunction "2_D2") (pintype "passive"))
      (node (ref "C3") (pin "2") (pinfunction "2_2") (pintype "passive"))
      (node (ref "C4") (pin "2") (pinfunction "2_2") (pintype "passive"))
      (node (ref "C5") (pin "1") (pinfunction "1_1") (pintype "passive"))
      (node (ref "C7") (pin "2") (pinfunction "2_2") (pintype "passive"))
      (node (ref "C8") (pin "2") (pinfunction "2_2") (pintype "passive"))
      (node (ref "CX2") (pin "1") (pinfunction "1_1") (pintype "passive"))
      (node (ref "CX3") (pin "1") (pinfunction "1_1") (pintype "passive"))
      (node (ref "IC1") (pin "18") (pinfunction "GND_18") (pintype "power_in"))
      (node (ref "IC1") (pin "28") (pinfunction "GND_28") (pintype "power_in"))
      (node (ref "IC1") (pin "39") (pinfunction "GND_39") (pintype "power_in"))
      (node (ref "IC1") (pin "6") (pinfunction "GND_6") (pintype "power_in"))
      (node (ref "IC1") (pin "TH") (pinfunction "EXP_TH") (pintype "power_in"))
      (node (ref "ISP2") (pin "6") (pinfunction "GND_6") (pintype "power_in"))
      (node (ref "J1") (pin "1") (pinfunction "1_1") (pintype "power_in"))
      (node (ref "J10") (pin "P$1") (pinfunction "1_P$1") (pintype "passive"))
      (node (ref "J10") (pin "P$10") (pinfunction "10_P$10") (pintype "passive"))
      (node (ref "J2") (pin "1") (pinfunction "1_1") (pintype "passive"))
      (node (ref "J4") (pin "1") (pinfunction "-_1") (pintype "bidirectional"))
      (node (ref "J6") (pin "GND") (pinfunction "GNDBREAK_GND") (pintype "bidirectional"))
      (node (ref "J6") (pin "P$4") (pinfunction "GND_P$4") (pintype "bidirectional"))
      (node (ref "J8") (pin "P$1") (pinfunction "1_P$1") (pintype "passive"))
      (node (ref "J8") (pin "P$7") (pinfunction "7_P$7") (pintype "passive"))
      (node (ref "J9") (pin "P$6") (pinfunction "6_P$6") (pintype "passive"))
      (node (ref "MICRO_USB") (pin "5") (pinfunction "GND_5") (pintype "power_in"))
      (node (ref "R1") (pin "1") (pinfunction "1_1") (pintype "passive"))
      (node (ref "R29") (pin "1") (pinfunction "1_1") (pintype "passive"))
      (node (ref "R47") (pin "2") (pinfunction "2_2") (pintype "passive"))
      (node (ref "RTC1") (pin "5") (pinfunction "GND_5") (pintype "power_in"))
      (node (ref "U$10") (pin "2") (pinfunction "GND_2") (pintype "bidirectional"))
      (node (ref "U$17") (pin "2") (pinfunction "GND_2") (pintype "power_in"))
      (node (ref "U$18") (pin "2") (pinfunction "GND_2") (pintype "power_in"))
      (node (ref "U$19") (pin "2") (pinfunction "GND_2") (pintype "power_in"))
      (node (ref "U$2") (pin "6") (pinfunction "VSS_6") (pintype "power_in"))
      (node (ref "U$2") (pin "MT1") (pinfunction "GND_MT1") (pintype "power_in"))
      (node (ref "U$2") (pin "MT2") (pinfunction "GND1_MT2") (pintype "power_in"))
      (node (ref "U$4") (pin "1") (pinfunction "PGND_1") (pintype "bidirectional"))
      (node (ref "U$4") (pin "4") (pinfunction "AGND_4") (pintype "bidirectional"))
      (node (ref "U$4") (pin "5") (pinfunction "FB_5") (pintype "bidirectional"))
      (node (ref "U$4") (pin "PAD") (pinfunction "PAD_PAD") (pintype "bidirectional"))
      (node (ref "U$5") (pin "1") (pinfunction "1_1") (pintype "bidirectional"))
      (node (ref "U$5") (pin "2") (pinfunction "2_2") (pintype "bidirectional"))
      (node (ref "U$6") (pin "1") (pinfunction "GND_1") (pintype "bidirectional"))
      (node (ref "U$6") (pin "10") (pinfunction "GND_10") (pintype "bidirectional"))
      (node (ref "U$6") (pin "11") (pinfunction "GND_11") (pintype "bidirectional"))
      (node (ref "U$6") (pin "15") (pinfunction "GND_15") (pintype "bidirectional"))
      (node (ref "U$6") (pin "16") (pinfunction "GND_16") (pintype "bidirectional"))
      (node (ref "U$6") (pin "20") (pinfunction "GND_20") (pintype "bidirectional"))
      (node (ref "U$6") (pin "4") (pinfunction "GND_4") (pintype "bidirectional"))
      (node (ref "U$6") (pin "5") (pinfunction "GND_5") (pintype "bidirectional"))
      (node (ref "U$6") (pin "6") (pinfunction "GND_6") (pintype "bidirectional"))
      (node (ref "U$7") (pin "1") (pinfunction "GND_1") (pintype "power_in"))
      (node (ref "U$7") (pin "30") (pinfunction "REF-_30") (pintype "input"))
      (node (ref "U$7") (pin "31") (pinfunction "GND_31") (pintype "power_in"))
      (node (ref "U$7") (pin "32") (pinfunction "GND_32") (pintype "power_in"))
      (node (ref "U$7") (pin "33") (pinfunction "GND_33") (pintype "power_in"))
      (node (ref "U$7") (pin "34") (pinfunction "GND_34") (pintype "power_in"))
      (node (ref "U$7") (pin "4") (pinfunction "GND_4") (pintype "power_in"))
      (node (ref "U$7") (pin "6") (pinfunction "GND_6") (pintype "power_in"))
      (node (ref "U$7") (pin "EXP") (pinfunction "GND_EXP") (pintype "power_in"))
      (node (ref "U$9") (pin "1") (pinfunction "1_1") (pintype "bidirectional"))
      (node (ref "U$9") (pin "2") (pinfunction "2_2") (pintype "bidirectional"))
      (node (ref "U2") (pin "13") (pinfunction "GND_13") (pintype "bidirectional"))
      (node (ref "U2") (pin "21") (pinfunction "GND_21") (pintype "bidirectional"))
      (node (ref "U2") (pin "3") (pinfunction "GND_3") (pintype "bidirectional"))
      (node (ref "U2") (pin "6") (pinfunction "CTS#_6") (pintype "bidirectional"))
      (node (ref "U3") (pin "1") (pinfunction "GND_1") (pintype "power_in"))
      (node (ref "U3") (pin "10") (pinfunction "GND_10") (pintype "power_in"))
      (node (ref "U3") (pin "8") (pinfunction "GND_8") (pintype "power_in"))
      (node (ref "U4") (pin "10") (pinfunction "ADDR1_10") (pintype "bidirectional"))
      (node (ref "U4") (pin "17") (pinfunction "GND_17") (pintype "bidirectional"))
      (node (ref "U4") (pin "26") (pinfunction "ADDR0_26") (pintype "bidirectional"))
      (node (ref "U4") (pin "29") (pinfunction "GND_29") (pintype "bidirectional"))
      (node (ref "U4") (pin "3") (pinfunction "GND_3") (pintype "bidirectional"))
      (node (ref "U6") (pin "7") (pinfunction "GND_7") (pintype "power_in"))
      (node (ref "U6") (pin "THERMAL@1") (pinfunction "PGND_THERMAL@1") (pintype "power_in"))
      (node (ref "U6") (pin "THERMAL@10") (pinfunction "PGND_THERMAL@10") (pintype "power_in"))
      (node (ref "U6") (pin "THERMAL@11") (pinfunction "PGND_THERMAL@11") (pintype "power_in"))
      (node (ref "U6") (pin "THERMAL@12") (pinfunction "PGND_THERMAL@12") (pintype "power_in"))
      (node (ref "U6") (pin "THERMAL@13") (pinfunction "PGND_THERMAL@13") (pintype "power_in"))
      (node (ref "U6") (pin "THERMAL@14") (pinfunction "PGND_THERMAL@14") (pintype "power_in"))
      (node (ref "U6") (pin "THERMAL@5") (pinfunction "PGND_THERMAL@5") (pintype "power_in"))
      (node (ref "U6") (pin "THERMAL@6") (pinfunction "PGND_THERMAL@6") (pintype "power_in"))
      (node (ref "U6") (pin "THERMAL@7") (pinfunction "PGND_THERMAL@7") (pintype "power_in"))
      (node (ref "U6") (pin "THERMAL@8") (pinfunction "PGND_THERMAL@8") (pintype "power_in"))
      (node (ref "U6") (pin "THERMAL@9") (pinfunction "PGND_THERMAL@9") (pintype "power_in"))
      (node (ref "X1") (pin "GND@1") (pinfunction "GND4_GND@1") (pintype "power_in"))
      (node (ref "X1") (pin "GND@2") (pinfunction "GND3_GND@2") (pintype "power_in"))
      (node (ref "X1") (pin "GND@3") (pinfunction "GND2_GND@3") (pintype "power_in"))
      (node (ref "X1") (pin "GND@4") (pinfunction "GND1_GND@4") (pintype "power_in"))
      (node (ref "X2") (pin "1") (pinfunction "1_1") (pintype "passive"))
    )
    (net (code "28") (name "GPIO_EXT1") (class "Default")
      (node (ref "J5") (pin "P$1") (pinfunction "1_P$1") (pintype "passive"))
      (node (ref "U4") (pin "19") (pinfunction "I/O[12]_19") (pintype "bidirectional"))
    )
    (net (code "29") (name "GPIO_EXT2") (class "Default")
      (node (ref "J5") (pin "P$2") (pinfunction "2_P$2") (pintype "passive"))
      (node (ref "U4") (pin "20") (pinfunction "I/O[13]_20") (pintype "bidirectional"))
    )
    (net (code "30") (name "GPIO_EXT3") (class "Default")
      (node (ref "J5") (pin "P$3") (pinfunction "3_P$3") (pintype "passive"))
      (node (ref "U4") (pin "21") (pinfunction "I/O[14]_21") (pintype "bidirectional"))
    )
    (net (code "31") (name "GPIO_EXT4") (class "Default")
      (node (ref "J5") (pin "P$4") (pinfunction "4_P$4") (pintype "passive"))
      (node (ref "U4") (pin "22") (pinfunction "I/O[15]_22") (pintype "bidirectional"))
    )
    (net (code "32") (name "LED1") (class "Default")
      (node (ref "R24") (pin "1") (pinfunction "1_1") (pintype "passive"))
      (node (ref "U4") (pin "6") (pinfunction "I/O[5]_6") (pintype "bidirectional"))
    )
    (net (code "33") (name "LED2") (class "Default")
      (node (ref "R14") (pin "1") (pinfunction "1_1") (pintype "passive"))
      (node (ref "U4") (pin "7") (pinfunction "I/O[6]_7") (pintype "bidirectional"))
    )
    (net (code "34") (name "LED3") (class "Default")
      (node (ref "R23") (pin "1") (pinfunction "1_1") (pintype "passive"))
      (node (ref "U4") (pin "8") (pinfunction "I/O[7]_8") (pintype "bidirectional"))
    )
    (net (code "35") (name "LOG_INT") (class "Default")
      (node (ref "IC1") (pin "34") (pinfunction "(PCINT3/ADC3)PA3_34") (pintype "bidirectional"))
      (node (ref "R13") (pin "1") (pinfunction "1_1") (pintype "passive"))
      (node (ref "U$5") (pin "3") (pinfunction "4_3") (pintype "bidirectional"))
      (node (ref "U$5") (pin "4") (pinfunction "3_4") (pintype "bidirectional"))
    )
    (net (code "36") (name "MISO") (class "Default")
      (node (ref "IC1") (pin "2") (pinfunction "(PCINT14/MISO)PB6_2") (pintype "bidirectional"))
      (node (ref "ISP2") (pin "1") (pinfunction "MISO_1") (pintype "input"))
      (node (ref "J10") (pin "P$2") (pinfunction "2_P$2") (pintype "passive"))
      (node (ref "J2") (pin "4") (pinfunction "4_4") (pintype "passive"))
      (node (ref "U$2") (pin "7") (pinfunction "DATA_OUT_7") (pintype "output"))
      (node (ref "U3") (pin "2") (pinfunction "MISO_2") (pintype "bidirectional"))
      (node (ref "X2") (pin "6") (pinfunction "6_6") (pintype "passive"))
    )
    (net (code "37") (name "MOSI") (class "Default")
      (node (ref "IC1") (pin "1") (pinfunction "(PCINT13/MOSI)PB5_1") (pintype "bidirectional"))
      (node (ref "ISP2") (pin "4") (pinfunction "MOSI_4") (pintype "output"))
      (node (ref "J10") (pin "P$3") (pinfunction "3_P$3") (pintype "passive"))
      (node (ref "J2") (pin "3") (pinfunction "3_3") (pintype "passive"))
      (node (ref "U$2") (pin "3") (pinfunction "DATA_IN_3") (pintype "input"))
      (node (ref "U3") (pin "3") (pinfunction "MOSI_3") (pintype "input"))
      (node (ref "X2") (pin "9") (pinfunction "9_9") (pintype "passive"))
    )
    (net (code "38") (name "MUX_INT") (class "Default")
      (node (ref "IC1") (pin "33") (pinfunction "(PCINT4/ADC4)PA4_33") (pintype "bidirectional"))
      (node (ref "R12") (pin "1") (pinfunction "1_1") (pintype "passive"))
      (node (ref "U4") (pin "9") (pinfunction "~{INT}_9") (pintype "bidirectional"))
    )
    (net (code "39") (name "Net-(C12A-2)") (class "Default")
      (node (ref "C12") (pin "A2") (pinfunction "2_A2") (pintype "passive"))
      (node (ref "R27") (pin "1") (pinfunction "1_1") (pintype "passive"))
    )
    (net (code "40") (name "Net-(C12B-2)") (class "Default")
      (node (ref "C12") (pin "B2") (pinfunction "2_B2") (pintype "passive"))
      (node (ref "R28") (pin "1") (pinfunction "1_1") (pintype "passive"))
    )
    (net (code "41") (name "Net-(C29A-1)") (class "Default")
      (node (ref "C29") (pin "A1") (pinfunction "1_A1") (pintype "passive"))
      (node (ref "R26") (pin "1") (pinfunction "1_1") (pintype "passive"))
    )
    (net (code "42") (name "Net-(C29B-1)") (class "Default")
      (node (ref "C29") (pin "B1") (pinfunction "1_B1") (pintype "passive"))
      (node (ref "R19") (pin "1") (pinfunction "1_1") (pintype "passive"))
    )
    (net (code "43") (name "Net-(C29C-1)") (class "Default")
      (node (ref "C29") (pin "C1") (pinfunction "1_C1") (pintype "passive"))
      (node (ref "R18") (pin "1") (pinfunction "1_1") (pintype "passive"))
    )
    (net (code "44") (name "Net-(C29D-1)") (class "Default")
      (node (ref "C29") (pin "D1") (pinfunction "1_D1") (pintype "passive"))
      (node (ref "R15") (pin "1") (pinfunction "1_1") (pintype "passive"))
    )
    (net (code "45") (name "Net-(IC1-XTAL1)") (class "Default")
      (node (ref "C25") (pin "2") (pinfunction "2_2") (pintype "passive"))
      (node (ref "IC1") (pin "8") (pinfunction "XTAL1_8") (pintype "bidirectional"))
      (node (ref "U$1") (pin "OSC1") (pinfunction "1_OSC1") (pintype "passive"))
    )
    (net (code "46") (name "Net-(IC1-XTAL2)") (class "Default")
      (node (ref "C5") (pin "2") (pinfunction "2_2") (pintype "passive"))
      (node (ref "IC1") (pin "7") (pinfunction "XTAL2_7") (pintype "bidirectional"))
      (node (ref "U$1") (pin "OSC2") (pinfunction "2_OSC2") (pintype "passive"))
    )
    (net (code "47") (name "Net-(L2-1)") (class "Default")
      (node (ref "L2") (pin "P$1") (pinfunction "1_P$1") (pintype "passive"))
      (node (ref "U$4") (pin "7") (pinfunction "SW_7") (pintype "bidirectional"))
    )
    (net (code "48") (name "Net-(MICRO_USB-D+)") (class "Default")
      (node (ref "CX3") (pin "2") (pinfunction "2_2") (pintype "passive"))
      (node (ref "D+") (pin "2") (pinfunction "2_2") (pintype "passive"))
      (node (ref "MICRO_USB") (pin "3") (pinfunction "D+_3") (pintype "bidirectional"))
    )
    (net (code "49") (name "Net-(MICRO_USB-D-)") (class "Default")
      (node (ref "CX2") (pin "2") (pinfunction "2_2") (pintype "passive"))
      (node (ref "D-") (pin "2") (pinfunction "2_2") (pintype "passive"))
      (node (ref "MICRO_USB") (pin "2") (pinfunction "D-_2") (pintype "bidirectional"))
    )
    (net (code "50") (name "Net-(Q5-D)") (class "Default")
      (node (ref "F1") (pin "1") (pinfunction "1_1") (pintype "bidirectional"))
      (node (ref "Q5") (pin "3") (pinfunction "D_3") (pintype "bidirectional"))
    )
    (net (code "51") (name "Net-(Q5-G)") (class "Default")
      (node (ref "Q5") (pin "1") (pinfunction "G_1") (pintype "bidirectional"))
      (node (ref "U$18") (pin "4") (pinfunction "OUT_4") (pintype "output"))
    )
    (net (code "52") (name "Net-(Q6-D)") (class "Default")
      (node (ref "F2") (pin "1") (pinfunction "1_1") (pintype "bidirectional"))
      (node (ref "Q6") (pin "3") (pinfunction "D_3") (pintype "bidirectional"))
    )
    (net (code "53") (name "Net-(Q6-G)") (class "Default")
      (node (ref "Q6") (pin "1") (pinfunction "G_1") (pintype "bidirectional"))
      (node (ref "U$17") (pin "4") (pinfunction "OUT_4") (pintype "output"))
    )
    (net (code "54") (name "Net-(Q7-G)") (class "Default")
      (node (ref "Q7") (pin "1") (pinfunction "G_1") (pintype "bidirectional"))
      (node (ref "U$19") (pin "4") (pinfunction "OUT_4") (pintype "output"))
    )
    (net (code "55") (name "Net-(RTC1-VBAT)") (class "Default")
      (node (ref "BT1") (pin "POWER0") (pinfunction "+_POWER0") (pintype "passive"))
      (node (ref "BT1") (pin "POWER1") (pinfunction "+_POWER1") (pintype "passive"))
      (node (ref "RTC1") (pin "6") (pinfunction "VBAT_6") (pintype "power_in"))
    )
    (net (code "56") (name "Net-(U$6-SCL)") (class "Default")
      (node (ref "R17") (pin "1") (pinfunction "1_1") (pintype "passive"))
      (node (ref "U$6") (pin "12") (pinfunction "SCL_12") (pintype "bidirectional"))
    )
    (net (code "57") (name "Net-(U$6-SDA)") (class "Default")
      (node (ref "R16") (pin "1") (pinfunction "1_1") (pintype "passive"))
      (node (ref "U$6") (pin "9") (pinfunction "SDA_9") (pintype "bidirectional"))
    )
    (net (code "58") (name "Net-(U$7-ADCINN)") (class "Default")
      (node (ref "U$7") (pin "26") (pinfunction "ADCINN_26") (pintype "bidirectional"))
      (node (ref "U$7") (pin "27") (pinfunction "MUXOUTN_27") (pintype "bidirectional"))
    )
    (net (code "59") (name "Net-(U$7-ADCINP)") (class "Default")
      (node (ref "U$7") (pin "24") (pinfunction "MUXOUTP_24") (pintype "bidirectional"))
      (node (ref "U$7") (pin "25") (pinfunction "ADCINP_25") (pintype "bidirectional"))
    )
    (net (code "60") (name "Net-(U$7-CH14)") (class "Default")
      (node (ref "R46") (pin "1") (pinfunction "1_1") (pintype "passive"))
      (node (ref "R47") (pin "1") (pinfunction "1_1") (pintype "passive"))
      (node (ref "U$7") (pin "22") (pinfunction "CH14_22") (pintype "input"))
    )
    (net (code "61") (name "Net-(U$8-1)") (class "Default")
      (node (ref "U$8") (pin "P$1") (pinfunction "1_P$1") (pintype "passive"))
      (node (ref "U6") (pin "1") (pinfunction "L1_1") (pintype "input"))
    )
    (net (code "62") (name "Net-(U$8-2)") (class "Default")
      (node (ref "U$8") (pin "P$2") (pinfunction "2_P$2") (pintype "passive"))
      (node (ref "U6") (pin "10") (pinfunction "L2_10") (pintype "input"))
    )
    (net (code "63") (name "Net-(U$10-FILT)") (class "Default")
      (node (ref "C22") (pin "1") (pinfunction "1_1") (pintype "passive"))
      (node (ref "U$10") (pin "1") (pinfunction "FILT_1") (pintype "bidirectional"))
    )
    (net (code "64") (name "Net-(U$10-OUTF)") (class "Default")
      (node (ref "C23") (pin "1") (pinfunction "1_1") (pintype "passive"))
      (node (ref "U$10") (pin "5") (pinfunction "OUTS_5") (pintype "bidirectional"))
      (node (ref "U$10") (pin "6") (pinfunction "OUTF_6") (pintype "bidirectional"))
      (node (ref "U$7") (pin "23") (pinfunction "CH15_23") (pintype "input"))
    )
    (net (code "65") (name "Net-(U$15-BLUE_CATH)") (class "Default")
      (node (ref "R14") (pin "2") (pinfunction "2_2") (pintype "passive"))
      (node (ref "U$15") (pin "3") (pinfunction "BLUE_CATH_3") (pintype "bidirectional"))
    )
    (net (code "66") (name "Net-(U$15-GREEN_CATH)") (class "Default")
      (node (ref "R23") (pin "2") (pinfunction "2_2") (pintype "passive"))
      (node (ref "U$15") (pin "4") (pinfunction "GREEN_CATH_4") (pintype "bidirectional"))
    )
    (net (code "67") (name "Net-(U$15-RED_CATH)") (class "Default")
      (node (ref "R24") (pin "2") (pinfunction "2_2") (pintype "passive"))
      (node (ref "U$15") (pin "1") (pinfunction "RED_CATH_1") (pintype "bidirectional"))
    )
    (net (code "68") (name "Net-(U$16-BLUE_CATH)") (class "Default")
      (node (ref "R4") (pin "1") (pinfunction "1_1") (pintype "passive"))
      (node (ref "U$16") (pin "3") (pinfunction "BLUE_CATH_3") (pintype "bidirectional"))
    )
    (net (code "69") (name "Net-(U$16-RED_CATH)") (class "Default")
      (node (ref "R5") (pin "1") (pinfunction "1_1") (pintype "passive"))
      (node (ref "U$16") (pin "1") (pinfunction "RED_CATH_1") (pintype "bidirectional"))
    )
    (net (code "70") (name "Net-(U2-3V3OUT)") (class "Default")
      (node (ref "C14") (pin "1") (pinfunction "1_1") (pintype "passive"))
      (node (ref "U2") (pin "10") (pinfunction "3V3OUT_10") (pintype "bidirectional"))
      (node (ref "U2") (pin "11") (pinfunction "RESET#_11") (pintype "bidirectional"))
      (node (ref "U2") (pin "20") (pinfunction "VCCIO_20") (pintype "bidirectional"))
    )
    (net (code "71") (name "Net-(U2-CBUS1)") (class "Default")
      (node (ref "R5") (pin "2") (pinfunction "2_2") (pintype "passive"))
      (node (ref "U2") (pin "14") (pinfunction "CBUS1_14") (pintype "bidirectional"))
    )
    (net (code "72") (name "Net-(U2-CBUS2)") (class "Default")
      (node (ref "R4") (pin "2") (pinfunction "2_2") (pintype "passive"))
      (node (ref "U2") (pin "7") (pinfunction "CBUS2_7") (pintype "bidirectional"))
    )
    (net (code "73") (name "Net-(U2-RXD)") (class "Default")
      (node (ref "R7") (pin "2") (pinfunction "2_2") (pintype "passive"))
      (node (ref "U2") (pin "1") (pinfunction "RXD_1") (pintype "bidirectional"))
    )
    (net (code "74") (name "Net-(U2-TXD)") (class "Default")
      (node (ref "R10") (pin "2") (pinfunction "2_2") (pintype "passive"))
      (node (ref "U2") (pin "17") (pinfunction "TXD_17") (pintype "bidirectional"))
    )
    (net (code "75") (name "Net-(U2-USBDM)") (class "Default")
      (node (ref "D-") (pin "1") (pinfunction "1_1") (pintype "passive"))
      (node (ref "U2") (pin "9") (pinfunction "USBDM_9") (pintype "bidirectional"))
    )
    (net (code "76") (name "Net-(U2-USBDP)") (class "Default")
      (node (ref "D+") (pin "1") (pinfunction "1_1") (pintype "passive"))
      (node (ref "U2") (pin "8") (pinfunction "USBDP_8") (pintype "bidirectional"))
    )
    (net (code "77") (name "Net-(U3-ANT)") (class "Default")
      (node (ref "U3") (pin "9") (pinfunction "ANT_9") (pintype "passive"))
      (node (ref "X1") (pin "P") (pinfunction "ANT_P") (pintype "bidirectional"))
    )
    (net (code "78") (name "Net-(U4-~{RESET})") (class "Default")
      (node (ref "R11") (pin "1") (pinfunction "1_1") (pintype "passive"))
      (node (ref "U4") (pin "23") (pinfunction "~{RESET}_23") (pintype "bidirectional"))
    )
    (net (code "79") (name "Net-(U6-FB)") (class "Default")
      (node (ref "C11") (pin "1") (pinfunction "1_1") (pintype "passive"))
      (node (ref "R1") (pin "2") (pinfunction "2_2") (pintype "passive"))
      (node (ref "R2") (pin "1") (pinfunction "1_1") (pintype "passive"))
      (node (ref "U6") (pin "8") (pinfunction "FB_8") (pintype "input"))
    )
    (net (code "80") (name "Net-(U6-VAUX)") (class "Default")
      (node (ref "C1") (pin "1") (pinfunction "1_1") (pintype "passive"))
      (node (ref "U6") (pin "6") (pinfunction "VAUX_6") (pintype "passive"))
    )
    (net (code "81") (name "RADIO_CS") (class "Default")
      (node (ref "IC1") (pin "26") (pinfunction "(PCINT23/TOSC2)PC7_26") (pintype "output"))
      (node (ref "U3") (pin "5") (pinfunction "NSS_5") (pintype "input"))
    )
    (net (code "82") (name "RADIO_INT") (class "Default")
      (node (ref "IC1") (pin "42") (pinfunction "(PCINT10/INT2/AIN0)PB2_42") (pintype "bidirectional"))
      (node (ref "U3") (pin "14") (pinfunction "DIO0_14") (pintype "bidirectional"))
    )
    (net (code "83") (name "REF_CTRL") (class "Default")
      (node (ref "U$10") (pin "3") (pinfunction "EN_3") (pintype "bidirectional"))
      (node (ref "U4") (pin "2") (pinfunction "I/O[3]_2") (pintype "bidirectional"))
    )
    (net (code "84") (name "RST") (class "Default")
      (node (ref "C6") (pin "2") (pinfunction "2_2") (pintype "passive"))
      (node (ref "IC1") (pin "4") (pinfunction "RESET_4") (pintype "input"))
      (node (ref "ISP2") (pin "5") (pinfunction "RST_5") (pintype "output"))
      (node (ref "R3") (pin "1") (pinfunction "1_1") (pintype "passive"))
      (node (ref "U$9") (pin "3") (pinfunction "4_3") (pintype "bidirectional"))
      (node (ref "U$9") (pin "4") (pinfunction "3_4") (pintype "bidirectional"))
    )
    (net (code "85") (name "RTC_INT") (class "Default")
      (node (ref "IC1") (pin "31") (pinfunction "(PCINT6/ADC6)PA6_31") (pintype "bidirectional"))
      (node (ref "RTC1") (pin "3") (pinfunction "SQW_3") (pintype "output"))
    )
    (net (code "86") (name "RX") (class "Default")
      (node (ref "IC1") (pin "9") (pinfunction "(PCINT24/RXD0)PD0_9") (pintype "bidirectional"))
      (node (ref "R10") (pin "1") (pinfunction "1_1") (pintype "passive"))
    )
    (net (code "87") (name "RX_EXT") (class "Default")
      (node (ref "IC1") (pin "11") (pinfunction "(PCINT26/INT0)PD2_11") (pintype "bidirectional"))
      (node (ref "J9") (pin "P$7") (pinfunction "7_P$7") (pintype "passive"))
      (node (ref "X2") (pin "7") (pinfunction "7_7") (pintype "passive"))
    )
    (net (code "88") (name "SCK") (class "Default")
      (node (ref "IC1") (pin "3") (pinfunction "(PCINT15/SCK)PB7_3") (pintype "bidirectional"))
      (node (ref "ISP2") (pin "3") (pinfunction "SCK_3") (pintype "output"))
      (node (ref "J10") (pin "P$4") (pinfunction "4_P$4") (pintype "passive"))
      (node (ref "J2") (pin "5") (pinfunction "5_5") (pintype "passive"))
      (node (ref "U$2") (pin "5") (pinfunction "SCLK_5") (pintype "input"))
      (node (ref "U3") (pin "4") (pinfunction "SCK_4") (pintype "input"))
      (node (ref "X2") (pin "10") (pinfunction "10_10") (pintype "passive"))
    )
    (net (code "89") (name "SCL") (class "Default")
      (node (ref "IC1") (pin "19") (pinfunction "(PCINT16/SCL)PC0_19") (pintype "output"))
      (node (ref "J1") (pin "4") (pinfunction "4_4") (pintype "passive"))
      (node (ref "J9") (pin "P$10") (pinfunction "10_P$10") (pintype "passive"))
      (node (ref "Q9") (pin "2") (pinfunction "S_2") (pintype "bidirectional"))
      (node (ref "R17") (pin "2") (pinfunction "2_2") (pintype "passive"))
      (node (ref "R42") (pin "1") (pinfunction "1_1") (pintype "passive"))
      (node (ref "RTC1") (pin "8") (pinfunction "SCL_8") (pintype "bidirectional"))
      (node (ref "U4") (pin "25") (pinfunction "SCL_25") (pintype "bidirectional"))
      (node (ref "X2") (pin "11") (pinfunction "11_11") (pintype "passive"))
    )
    (net (code "90") (name "SCL_HV") (class "Default")
      (node (ref "Q9") (pin "3") (pinfunction "D_3") (pintype "bidirectional"))
      (node (ref "R9") (pin "1") (pinfunction "1_1") (pintype "passive"))
      (node (ref "U$7") (pin "2") (pinfunction "SCL_2") (pintype "bidirectional"))
    )
    (net (code "91") (name "SDA") (class "Default")
      (node (ref "IC1") (pin "20") (pinfunction "(PCINT17/SDA)PC1_20") (pintype "output"))
      (node (ref "J1") (pin "3") (pinfunction "3_3") (pintype "passive"))
      (node (ref "J9") (pin "P$9") (pinfunction "9_P$9") (pintype "passive"))
      (node (ref "Q8") (pin "2") (pinfunction "S_2") (pintype "bidirectional"))
      (node (ref "R16") (pin "2") (pinfunction "2_2") (pintype "passive"))
      (node (ref "R43") (pin "1") (pinfunction "1_1") (pintype "passive"))
      (node (ref "RTC1") (pin "7") (pinfunction "SDA_7") (pintype "bidirectional"))
      (node (ref "U4") (pin "24") (pinfunction "SDA_24") (pintype "bidirectional"))
      (node (ref "X2") (pin "4") (pinfunction "4_4") (pintype "passive"))
    )
    (net (code "92") (name "SDA_HV") (class "Default")
      (node (ref "Q8") (pin "3") (pinfunction "D_3") (pintype "bidirectional"))
      (node (ref "R8") (pin "1") (pinfunction "1_1") (pintype "passive"))
      (node (ref "U$7") (pin "3") (pinfunction "SDA_3") (pintype "bidirectional"))
    )
    (net (code "93") (name "SD_CD") (class "Default")
      (node (ref "U$2") (pin "CD1") (pinfunction "CARD_DETECT_CD1") (pintype "passive"))
    )
    (net (code "94") (name "SD_CS") (class "Default")
      (node (ref "IC1") (pin "13") (pinfunction "(PCINT28/OC1B)PD4_13") (pintype "bidirectional"))
      (node (ref "U$2") (pin "2") (pinfunction "CS_2") (pintype "input"))
    )
    (net (code "95") (name "SD_VCC") (class "Default")
      (node (ref "Q7") (pin "3") (pinfunction "D_3") (pintype "bidirectional"))
      (node (ref "U$2") (pin "4") (pinfunction "VDD_4") (pintype "power_in"))
    )
    (net (code "96") (name "SD_VCC_CTRL") (class "Default")
      (node (ref "U$19") (pin "1") (pinfunction "INP_1") (pintype "input"))
      (node (ref "U4") (pin "1") (pinfunction "I/O[2]_1") (pintype "bidirectional"))
    )
    (net (code "97") (name "SPI_EXT_CS1") (class "Default")
      (node (ref "J2") (pin "6") (pinfunction "6_6") (pintype "passive"))
      (node (ref "U4") (pin "16") (pinfunction "I/O[11]_16") (pintype "bidirectional"))
    )
    (net (code "98") (name "SPI_EXT_CS2") (class "Default")
      (node (ref "J10") (pin "P$6") (pinfunction "6_P$6") (pintype "passive"))
      (node (ref "U4") (pin "14") (pinfunction "I/O[9]_14") (pintype "bidirectional"))
    )
    (net (code "99") (name "SS") (class "Default")
      (node (ref "IC1") (pin "44") (pinfunction "(PCINT12/OC0B/~{SS})PB4_44") (pintype "bidirectional"))
    )
    (net (code "100") (name "TX") (class "Default")
      (node (ref "IC1") (pin "10") (pinfunction "(PCINT25/TXD0)PD1_10") (pintype "bidirectional"))
      (node (ref "R7") (pin "1") (pinfunction "1_1") (pintype "passive"))
    )
    (net (code "101") (name "TX_EXT") (class "Default")
      (node (ref "IC1") (pin "12") (pinfunction "(PCINT27/INT1)PD3_12") (pintype "bidirectional"))
      (node (ref "J9") (pin "P$8") (pinfunction "8_P$8") (pintype "passive"))
      (node (ref "X2") (pin "8") (pinfunction "8_8") (pintype "passive"))
    )
    (net (code "102") (name "unconnected-(C12C-1-PadC1)") (class "Default")
      (node (ref "C12") (pin "C1") (pinfunction "1_C1") (pintype "passive"))
    )
    (net (code "103") (name "unconnected-(C12C-2-PadC2)") (class "Default")
      (node (ref "C12") (pin "C2") (pinfunction "2_C2") (pintype "passive"))
    )
    (net (code "104") (name "unconnected-(C12D-1-PadD1)") (class "Default")
      (node (ref "C12") (pin "D1") (pinfunction "1_D1") (pintype "passive"))
    )
    (net (code "105") (name "unconnected-(C12D-2-PadD2)") (class "Default")
      (node (ref "C12") (pin "D2") (pinfunction "2_D2") (pintype "passive"))
    )
    (net (code "106") (name "unconnected-(IC1-(PCINT0{slash}ADC0)PA0-Pad37)") (class "Default")
      (node (ref "IC1") (pin "37") (pinfunction "(PCINT0/ADC0)PA0_37") (pintype "bidirectional"))
    )
    (net (code "107") (name "unconnected-(IC1-(PCINT1{slash}ADC1)PA1-Pad36)") (class "Default")
      (node (ref "IC1") (pin "36") (pinfunction "(PCINT1/ADC1)PA1_36") (pintype "bidirectional"))
    )
    (net (code "108") (name "unconnected-(IC1-(PCINT2{slash}ADC2)PA2-Pad35)") (class "Default")
      (node (ref "IC1") (pin "35") (pinfunction "(PCINT2/ADC2)PA2_35") (pintype "bidirectional"))
    )
    (net (code "109") (name "unconnected-(IC1-(PCINT5{slash}ADC5)PA5-Pad32)") (class "Default")
      (node (ref "IC1") (pin "32") (pinfunction "(PCINT5/ADC5)PA5_32") (pintype "bidirectional"))
    )
    (net (code "110") (name "unconnected-(IC1-(PCINT11{slash}OC0A{slash}AIN1)PB3-Pad43)") (class "Default")
      (node (ref "IC1") (pin "43") (pinfunction "(PCINT11/OC0A/AIN1)PB3_43") (pintype "bidirectional"))
    )
    (net (code "111") (name "unconnected-(IC1-(PCINT18{slash}TCK)PC2-Pad21)") (class "Default")
      (node (ref "IC1") (pin "21") (pinfunction "(PCINT18/TCK)PC2_21") (pintype "output"))
    )
    (net (code "112") (name "unconnected-(IC1-(PCINT19{slash}TMS)PC3-Pad22)") (class "Default")
      (node (ref "IC1") (pin "22") (pinfunction "(PCINT19/TMS)PC3_22") (pintype "output"))
    )
    (net (code "113") (name "unconnected-(IC1-(PCINT20{slash}TDO)PC4-Pad23)") (class "Default")
      (node (ref "IC1") (pin "23") (pinfunction "(PCINT20/TDO)PC4_23") (pintype "output"))
    )
    (net (code "114") (name "unconnected-(IC1-(PCINT21{slash}TDI)PC5-Pad24)") (class "Default")
      (node (ref "IC1") (pin "24") (pinfunction "(PCINT21/TDI)PC5_24") (pintype "output"))
    )
    (net (code "115") (name "unconnected-(IC1-(PCINT22{slash}TOSC1)PC6-Pad25)") (class "Default")
      (node (ref "IC1") (pin "25") (pinfunction "(PCINT22/TOSC1)PC6_25") (pintype "output"))
    )
    (net (code "116") (name "unconnected-(IC1-(PCINT29{slash}OC1A)PD5-Pad14)") (class "Default")
      (node (ref "IC1") (pin "14") (pinfunction "(PCINT29/OC1A)PD5_14") (pintype "bidirectional"))
    )
    (net (code "117") (name "unconnected-(IC1-(PCINT30{slash}OC2B{slash}ICP)PD6-Pad15)") (class "Default")
      (node (ref "IC1") (pin "15") (pinfunction "(PCINT30/OC2B/ICP)PD6_15") (pintype "bidirectional"))
    )
    (net (code "118") (name "unconnected-(IC1-(PCINT31{slash}OC2A)PD7-Pad16)") (class "Default")
      (node (ref "IC1") (pin "16") (pinfunction "(PCINT31/OC2A)PD7_16") (pintype "bidirectional"))
    )
    (net (code "119") (name "unconnected-(J4-PAD1-PadNC1)") (class "Default")
      (node (ref "J4") (pin "NC1") (pinfunction "PAD1_NC1") (pintype "bidirectional"))
    )
    (net (code "120") (name "unconnected-(J4-PAD2-PadNC2)") (class "Default")
      (node (ref "J4") (pin "NC2") (pinfunction "PAD2_NC2") (pintype "bidirectional"))
    )
    (net (code "121") (name "unconnected-(MICRO_USB-ID-Pad4)") (class "Default")
      (node (ref "MICRO_USB") (pin "4") (pinfunction "ID_4") (pintype "passive"))
    )
    (net (code "122") (name "unconnected-(RTC1-32KHZ-Pad1)") (class "Default")
      (node (ref "RTC1") (pin "1") (pinfunction "32KHZ_1") (pintype "output"))
    )
    (net (code "123") (name "unconnected-(RTC1-RST-Pad4)") (class "Default")
      (node (ref "RTC1") (pin "4") (pinfunction "RST_4") (pintype "bidirectional"))
    )
    (net (code "124") (name "unconnected-(U$2-CARD_DETECT1-PadCD2)") (class "Default")
      (node (ref "U$2") (pin "CD2") (pinfunction "CARD_DETECT1_CD2") (pintype "passive"))
    )
    (net (code "125") (name "unconnected-(U$2-DAT1-Pad8)") (class "Default")
      (node (ref "U$2") (pin "8") (pinfunction "DAT1_8") (pintype "bidirectional"))
    )
    (net (code "126") (name "unconnected-(U$2-DAT2-Pad1)") (class "Default")
      (node (ref "U$2") (pin "1") (pinfunction "DAT2_1") (pintype "bidirectional"))
    )
    (net (code "127") (name "unconnected-(U$4-PG-Pad8)") (class "Default")
      (node (ref "U$4") (pin "8") (pinfunction "PG_8") (pintype "bidirectional"))
    )
    (net (code "128") (name "unconnected-(U$6-EXTINT0-Pad19)") (class "Default")
      (node (ref "U$6") (pin "19") (pinfunction "EXTINT0_19") (pintype "bidirectional"))
    )
    (net (code "129") (name "unconnected-(U$6-RESET_N-Pad18)") (class "Default")
      (node (ref "U$6") (pin "18") (pinfunction "RESET_N_18") (pintype "bidirectional"))
    )
    (net (code "130") (name "unconnected-(U$6-RXD-Pad14)") (class "Default")
      (node (ref "U$6") (pin "14") (pinfunction "RXD_14") (pintype "bidirectional"))
    )
    (net (code "131") (name "unconnected-(U$6-SAFEBOOT_N-Pad8)") (class "Default")
      (node (ref "U$6") (pin "8") (pinfunction "SAFEBOOT_N_8") (pintype "bidirectional"))
    )
    (net (code "132") (name "unconnected-(U$6-TIMEPULSE-Pad7)") (class "Default")
      (node (ref "U$6") (pin "7") (pinfunction "TIMEPULSE_7") (pintype "bidirectional"))
    )
    (net (code "133") (name "unconnected-(U$6-TXD-Pad13)") (class "Default")
      (node (ref "U$6") (pin "13") (pinfunction "TXD_13") (pintype "bidirectional"))
    )
    (net (code "134") (name "unconnected-(U$7-CA0-Pad36)") (class "Default")
      (node (ref "U$7") (pin "36") (pinfunction "CA0_36") (pintype "input"))
    )
    (net (code "135") (name "unconnected-(U$7-CA1-Pad37)") (class "Default")
      (node (ref "U$7") (pin "37") (pinfunction "CA1_37") (pintype "input"))
    )
    (net (code "136") (name "unconnected-(U$7-CA2-Pad38)") (class "Default")
      (node (ref "U$7") (pin "38") (pinfunction "CA2_38") (pintype "input"))
    )
    (net (code "137") (name "unconnected-(U$7-CH12-Pad20)") (class "Default")
      (node (ref "U$7") (pin "20") (pinfunction "CH12_20") (pintype "input"))
    )
    (net (code "138") (name "unconnected-(U$7-CH13-Pad21)") (class "Default")
      (node (ref "U$7") (pin "21") (pinfunction "CH13_21") (pintype "input"))
    )
    (net (code "139") (name "unconnected-(U$7-F0-Pad35)") (class "Default")
      (node (ref "U$7") (pin "35") (pinfunction "F0_35") (pintype "input"))
    )
    (net (code "140") (name "unconnected-(U$16-GREEN_CATH-Pad4)") (class "Default")
      (node (ref "U$16") (pin "4") (pinfunction "GREEN_CATH_4") (pintype "bidirectional"))
    )
    (net (code "141") (name "unconnected-(U2-CBUS0-Pad15)") (class "Default")
      (node (ref "U2") (pin "15") (pinfunction "CBUS0_15") (pintype "bidirectional"))
    )
    (net (code "142") (name "unconnected-(U2-CBUS3-Pad16)") (class "Default")
      (node (ref "U2") (pin "16") (pinfunction "CBUS3_16") (pintype "bidirectional"))
    )
    (net (code "143") (name "unconnected-(U2-DCD#-Pad5)") (class "Default")
      (node (ref "U2") (pin "5") (pinfunction "DCD#_5") (pintype "bidirectional"))
    )
    (net (code "144") (name "unconnected-(U2-DSR#-Pad4)") (class "Default")
      (node (ref "U2") (pin "4") (pinfunction "DSR#_4") (pintype "bidirectional"))
    )
    (net (code "145") (name "unconnected-(U2-RI#-Pad2)") (class "Default")
      (node (ref "U2") (pin "2") (pinfunction "RI#_2") (pintype "bidirectional"))
    )
    (net (code "146") (name "unconnected-(U2-RTS#-Pad19)") (class "Default")
      (node (ref "U2") (pin "19") (pinfunction "RTS#_19") (pintype "bidirectional"))
    )
    (net (code "147") (name "unconnected-(U3-DIO1-Pad15)") (class "Default")
      (node (ref "U3") (pin "15") (pinfunction "DIO1_15") (pintype "bidirectional"))
    )
    (net (code "148") (name "unconnected-(U3-DIO2-Pad16)") (class "Default")
      (node (ref "U3") (pin "16") (pinfunction "DIO2_16") (pintype "bidirectional"))
    )
    (net (code "149") (name "unconnected-(U3-DIO3-Pad11)") (class "Default")
      (node (ref "U3") (pin "11") (pinfunction "DIO3_11") (pintype "bidirectional"))
    )
    (net (code "150") (name "unconnected-(U3-DIO4-Pad12)") (class "Default")
      (node (ref "U3") (pin "12") (pinfunction "DIO4_12") (pintype "bidirectional"))
    )
    (net (code "151") (name "unconnected-(U3-DIO5-Pad7)") (class "Default")
      (node (ref "U3") (pin "7") (pinfunction "DIO5_7") (pintype "bidirectional"))
    )
    (net (code "152") (name "unconnected-(U3-RESET-Pad6)") (class "Default")
      (node (ref "U3") (pin "6") (pinfunction "RESET_6") (pintype "input"))
    )
    (net (code "153") (name "unconnected-(U4-I{slash}O[1]-Pad28)") (class "Default")
      (node (ref "U4") (pin "28") (pinfunction "I/O[1]_28") (pintype "bidirectional"))
    )
    (net (code "154") (name "unconnected-(U4-OSCIO-Pad11)") (class "Default")
      (node (ref "U4") (pin "11") (pinfunction "OSCIO_11") (pintype "bidirectional"))
    )
    (net (code "155") (name "unconnected-(U6-PG-Pad5)") (class "Default")
      (node (ref "U6") (pin "5") (pinfunction "PG_5") (pintype "open_collector"))
    )
  )
)
